# 8051.net
KiCad netlist of a schematic drawn in EAGLE
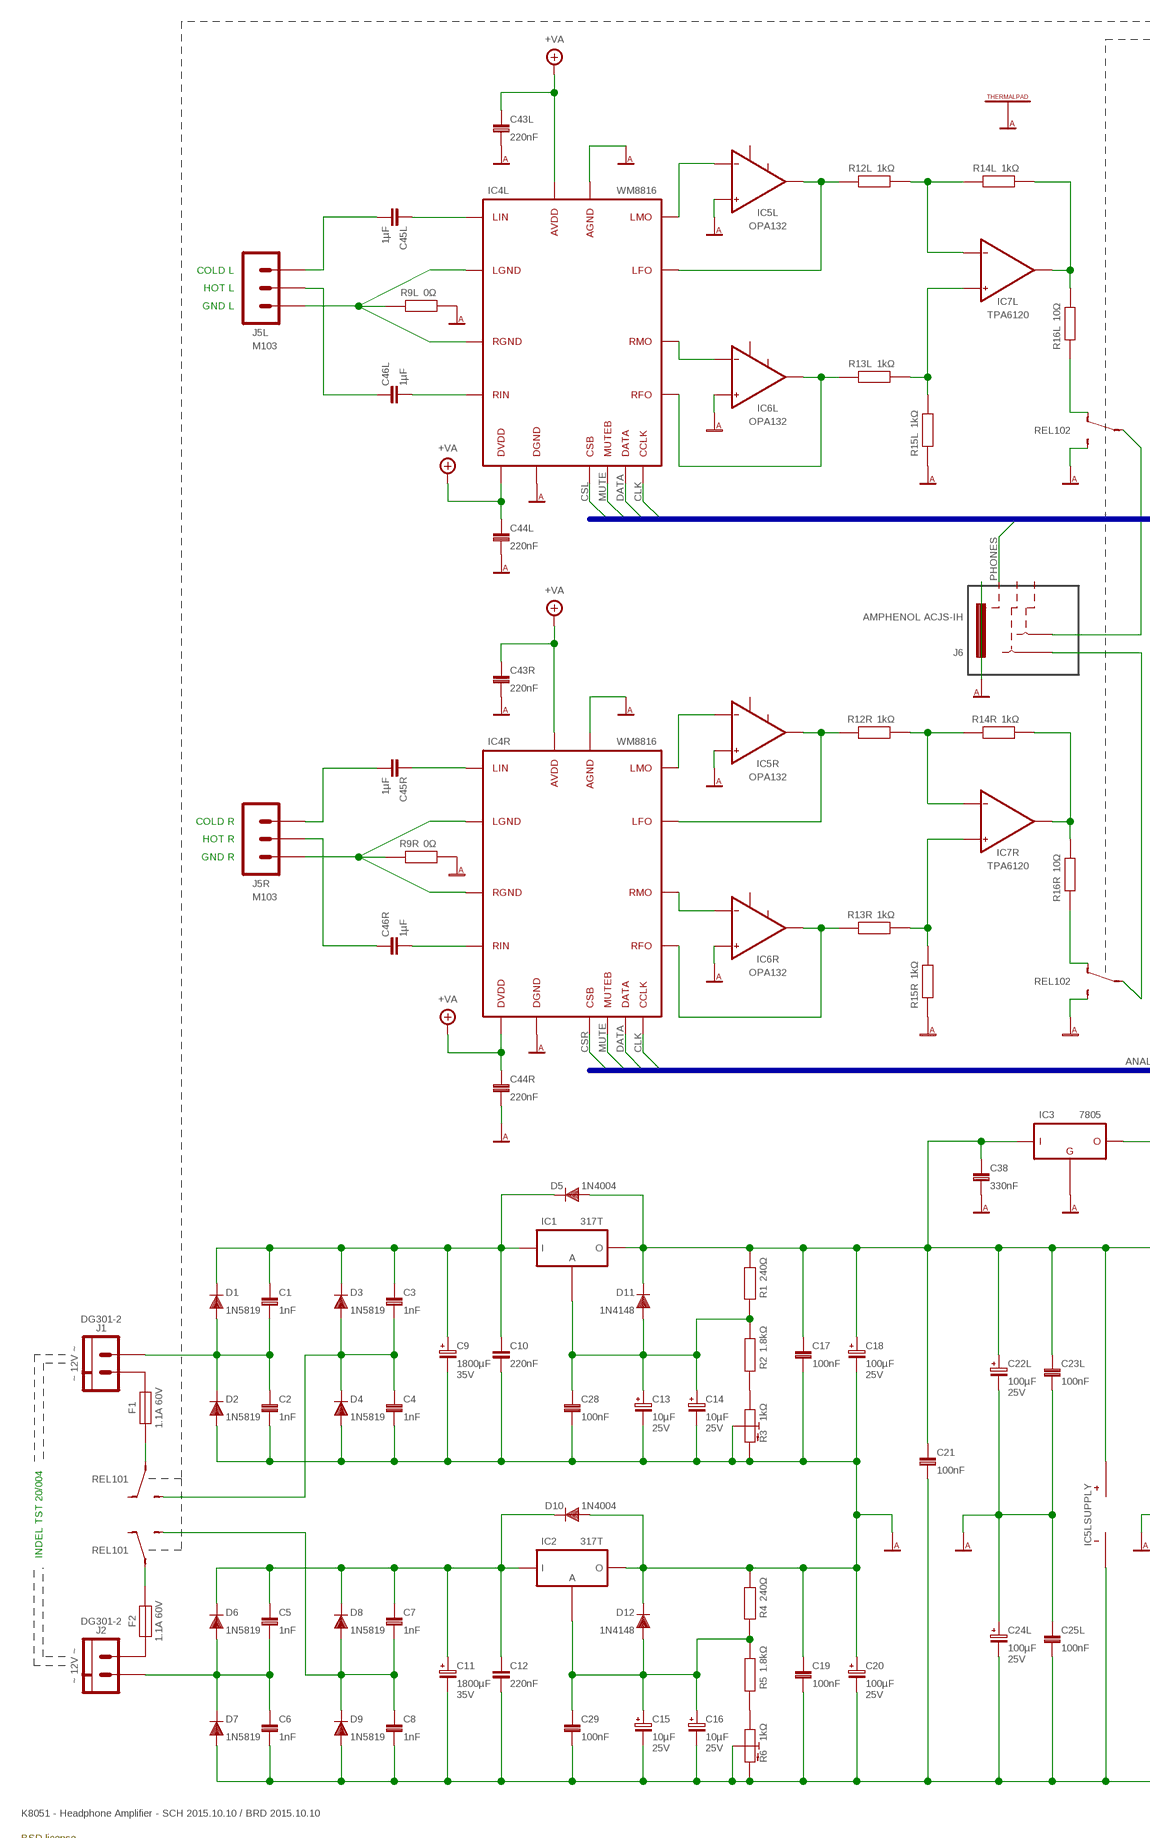
[diagram p0: schematic, sheet 1, part 1 of 2]
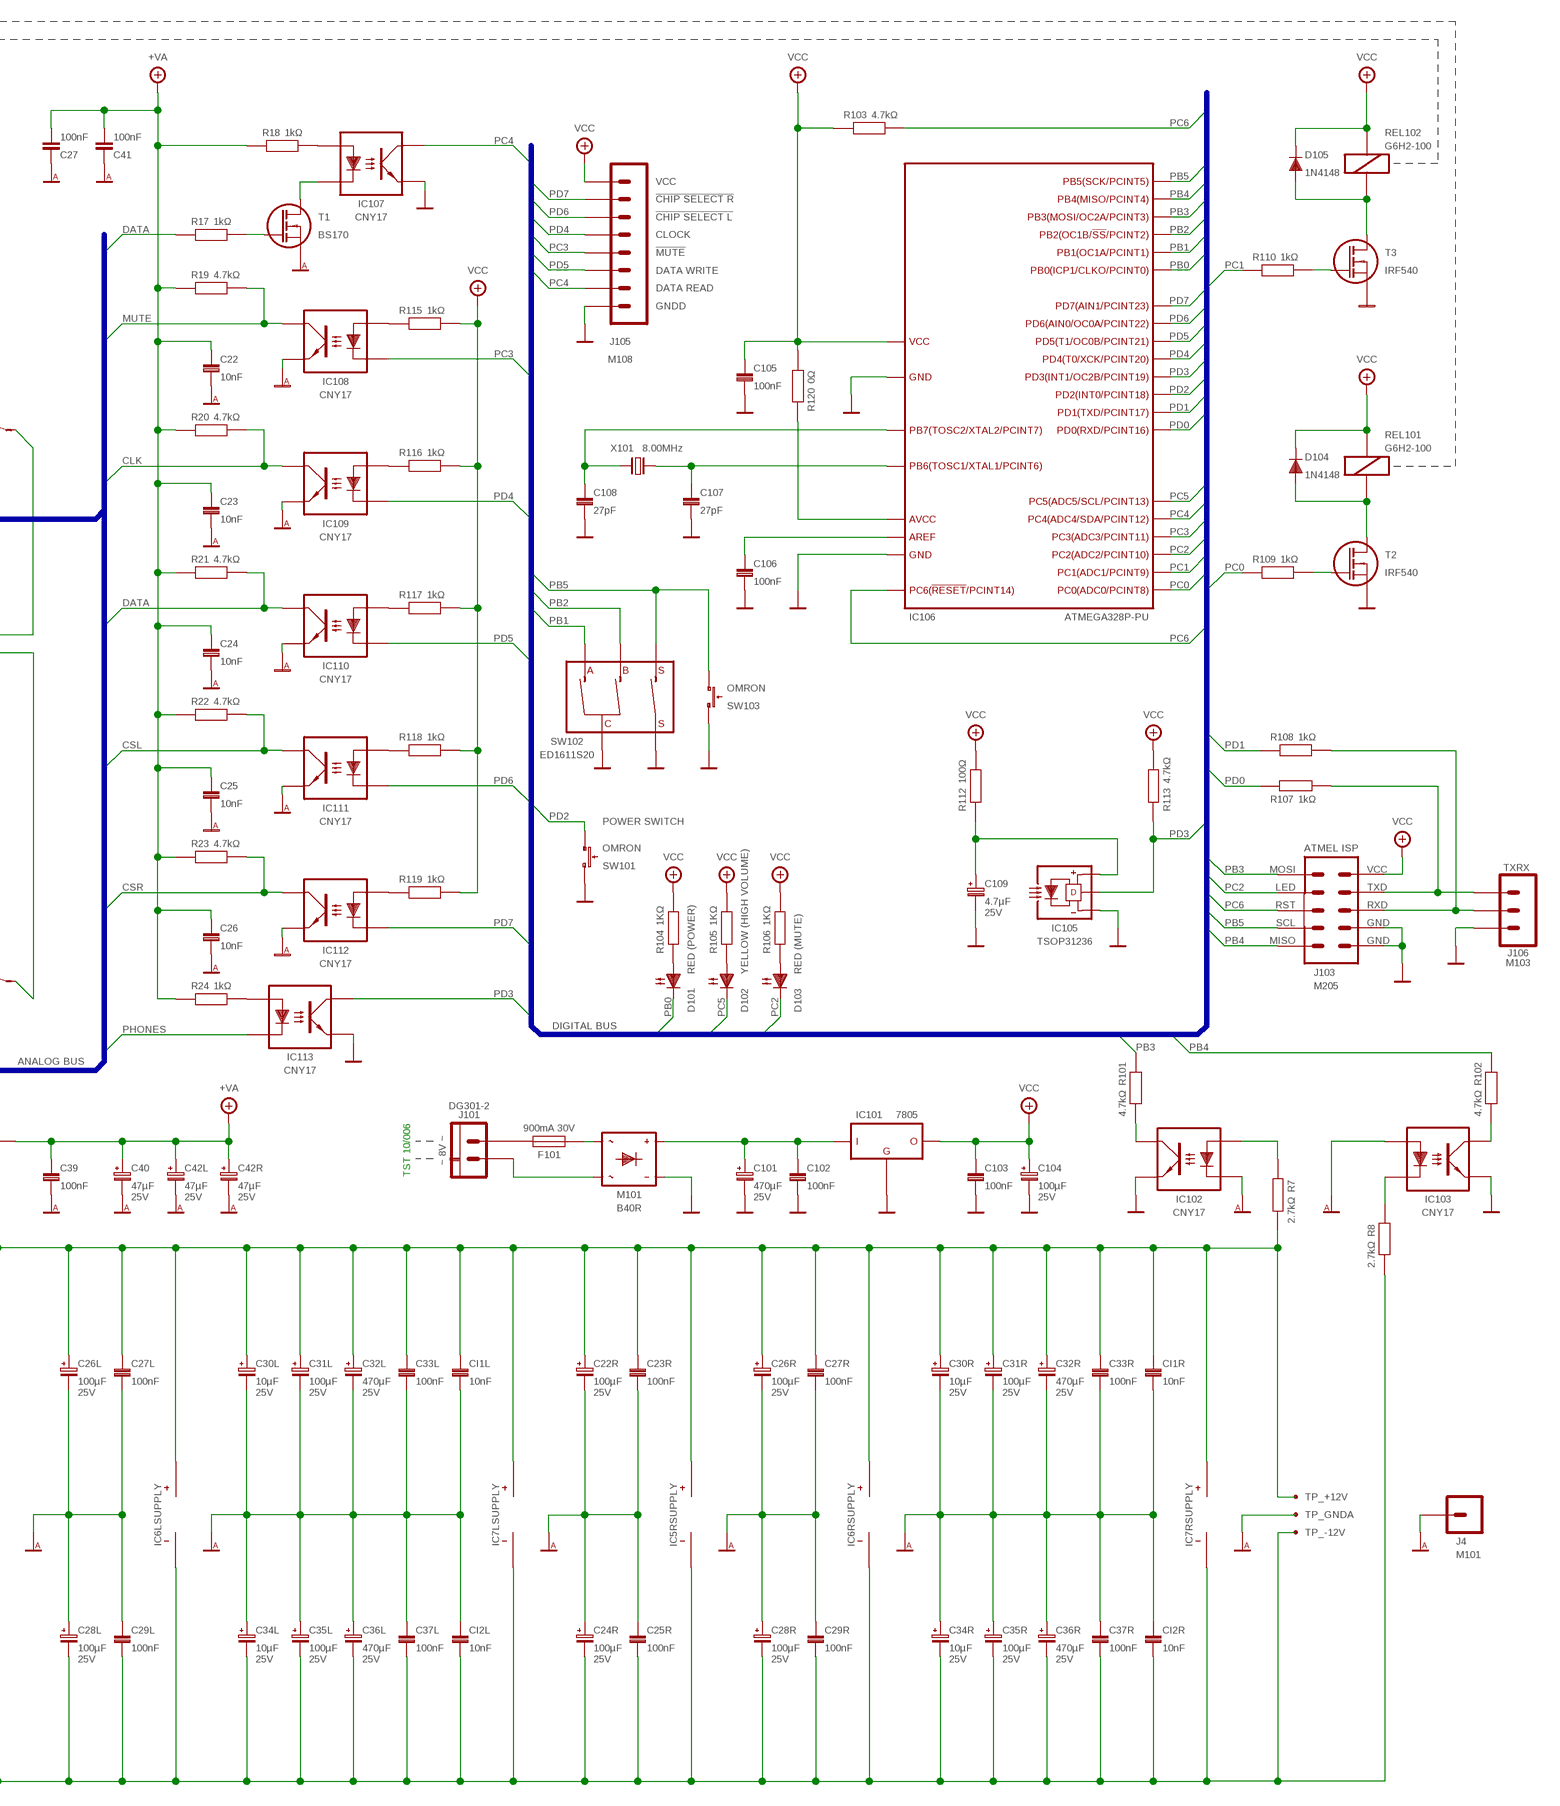
[diagram p1: schematic, sheet 1, part 2 of 2]

(export (version "E")
  (design (tool "Eeschema 10.0.6"))
  (components
    (comp (ref "C1")
      (value "1nF")
      (footprint "eagle-import:C075-032X103")
      (libsource (lib "eagle-import") (part "C075-032X103"))
    )
    (comp (ref "C2")
      (value "1nF")
      (footprint "eagle-import:C075-032X103")
      (libsource (lib "eagle-import") (part "C075-032X103"))
    )
    (comp (ref "C3")
      (value "1nF")
      (footprint "eagle-import:C075-032X103")
      (libsource (lib "eagle-import") (part "C075-032X103"))
    )
    (comp (ref "C4")
      (value "1nF")
      (footprint "eagle-import:C075-032X103")
      (libsource (lib "eagle-import") (part "C075-032X103"))
    )
    (comp (ref "C5")
      (value "1nF")
      (footprint "eagle-import:C075-032X103")
      (libsource (lib "eagle-import") (part "C075-032X103"))
    )
    (comp (ref "C6")
      (value "1nF")
      (footprint "eagle-import:C075-032X103")
      (libsource (lib "eagle-import") (part "C075-032X103"))
    )
    (comp (ref "C7")
      (value "1nF")
      (footprint "eagle-import:C075-032X103")
      (libsource (lib "eagle-import") (part "C075-032X103"))
    )
    (comp (ref "C8")
      (value "1nF")
      (footprint "eagle-import:C075-032X103")
      (libsource (lib "eagle-import") (part "C075-032X103"))
    )
    (comp (ref "C9")
      (value "1800µF")
      (footprint "eagle-import:E-160-250-075-08")
      (fields (field (name "VOLTAGE") "35V"))
      (libsource (lib "eagle-import") (part "FM1V182"))
    )
    (comp (ref "C10")
      (value "220nF")
      (footprint "eagle-import:C102-064X133")
      (libsource (lib "eagle-import") (part "C102-064X133"))
    )
    (comp (ref "C11")
      (value "1800µF")
      (footprint "eagle-import:E-160-250-075-08")
      (fields (field (name "VOLTAGE") "35V"))
      (libsource (lib "eagle-import") (part "FM1V182"))
    )
    (comp (ref "C12")
      (value "220nF")
      (footprint "eagle-import:C102-064X133")
      (libsource (lib "eagle-import") (part "C102-064X133"))
    )
    (comp (ref "C13")
      (value "10µF")
      (footprint "eagle-import:E-050-110-020-05")
      (fields (field (name "VOLTAGE") "25V") (field (name "VOLTAGE_1") "25V"))
      (libsource (lib "eagle-import") (part "FM1E470"))
    )
    (comp (ref "C14")
      (value "10µF")
      (footprint "eagle-import:E-050-110-020-05")
      (fields (field (name "VOLTAGE") "25V") (field (name "VOLTAGE_1") "25V"))
      (libsource (lib "eagle-import") (part "FM1E470"))
    )
    (comp (ref "C15")
      (value "10µF")
      (footprint "eagle-import:E-050-110-020-05")
      (fields (field (name "VOLTAGE") "25V") (field (name "VOLTAGE_1") "25V"))
      (libsource (lib "eagle-import") (part "FM1E470"))
    )
    (comp (ref "C16")
      (value "10µF")
      (footprint "eagle-import:E-050-110-020-05")
      (fields (field (name "VOLTAGE") "25V") (field (name "VOLTAGE_1") "25V"))
      (libsource (lib "eagle-import") (part "FM1E470"))
    )
    (comp (ref "C17")
      (value "100nF")
      (footprint "eagle-import:C075-042X103")
      (libsource (lib "eagle-import") (part "C075-042X103"))
    )
    (comp (ref "C18")
      (value "100µF")
      (footprint "eagle-import:E-063-112-025-05")
      (fields (field (name "VOLTAGE") "25V") (field (name "VOLTAGE_1") "25V"))
      (libsource (lib "eagle-import") (part "FM1E101"))
    )
    (comp (ref "C19")
      (value "100nF")
      (footprint "eagle-import:C075-042X103")
      (libsource (lib "eagle-import") (part "C075-042X103"))
    )
    (comp (ref "C20")
      (value "100µF")
      (footprint "eagle-import:E-063-112-025-05")
      (fields (field (name "VOLTAGE") "25V") (field (name "VOLTAGE_1") "25V"))
      (libsource (lib "eagle-import") (part "FM1E101"))
    )
    (comp (ref "C21")
      (value "100nF")
      (footprint "eagle-import:C075-042X103")
      (libsource (lib "eagle-import") (part "C075-042X103"))
    )
    (comp (ref "C22")
      (value "10nF")
      (footprint "eagle-import:C0805")
      (libsource (lib "eagle-import") (part "CC0805"))
    )
    (comp (ref "C22L")
      (value "100µF")
      (footprint "eagle-import:E-063-112-025-05")
      (fields (field (name "VOLTAGE") "25V") (field (name "VOLTAGE_1") "25V"))
      (libsource (lib "eagle-import") (part "FM1E101"))
    )
    (comp (ref "C22R")
      (value "100µF")
      (footprint "eagle-import:E-063-112-025-05")
      (fields (field (name "VOLTAGE") "25V") (field (name "VOLTAGE_1") "25V"))
      (libsource (lib "eagle-import") (part "FM1E101"))
    )
    (comp (ref "C23")
      (value "10nF")
      (footprint "eagle-import:C0805")
      (libsource (lib "eagle-import") (part "CC0805"))
    )
    (comp (ref "C23L")
      (value "100nF")
      (footprint "eagle-import:C075-042X103")
      (libsource (lib "eagle-import") (part "C075-042X103"))
    )
    (comp (ref "C23R")
      (value "100nF")
      (footprint "eagle-import:C075-042X103")
      (libsource (lib "eagle-import") (part "C075-042X103"))
    )
    (comp (ref "C24")
      (value "10nF")
      (footprint "eagle-import:C0805")
      (libsource (lib "eagle-import") (part "CC0805"))
    )
    (comp (ref "C24L")
      (value "100µF")
      (footprint "eagle-import:E-063-112-025-05")
      (fields (field (name "VOLTAGE") "25V") (field (name "VOLTAGE_1") "25V"))
      (libsource (lib "eagle-import") (part "FM1E101"))
    )
    (comp (ref "C24R")
      (value "100µF")
      (footprint "eagle-import:E-063-112-025-05")
      (fields (field (name "VOLTAGE") "25V") (field (name "VOLTAGE_1") "25V"))
      (libsource (lib "eagle-import") (part "FM1E101"))
    )
    (comp (ref "C25")
      (value "10nF")
      (footprint "eagle-import:C0805")
      (libsource (lib "eagle-import") (part "CC0805"))
    )
    (comp (ref "C25L")
      (value "100nF")
      (footprint "eagle-import:C075-042X103")
      (libsource (lib "eagle-import") (part "C075-042X103"))
    )
    (comp (ref "C25R")
      (value "100nF")
      (footprint "eagle-import:C075-042X103")
      (libsource (lib "eagle-import") (part "C075-042X103"))
    )
    (comp (ref "C26")
      (value "10nF")
      (footprint "eagle-import:C0805")
      (libsource (lib "eagle-import") (part "CC0805"))
    )
    (comp (ref "C26L")
      (value "100µF")
      (footprint "eagle-import:E-063-112-025-05")
      (fields (field (name "VOLTAGE") "25V") (field (name "VOLTAGE_1") "25V"))
      (libsource (lib "eagle-import") (part "FM1E101"))
    )
    (comp (ref "C26R")
      (value "100µF")
      (footprint "eagle-import:E-063-112-025-05")
      (fields (field (name "VOLTAGE") "25V") (field (name "VOLTAGE_1") "25V"))
      (libsource (lib "eagle-import") (part "FM1E101"))
    )
    (comp (ref "C27")
      (value "100nF")
      (footprint "eagle-import:C075-042X103")
      (libsource (lib "eagle-import") (part "C075-042X103"))
    )
    (comp (ref "C27L")
      (value "100nF")
      (footprint "eagle-import:C075-042X103")
      (libsource (lib "eagle-import") (part "C075-042X103"))
    )
    (comp (ref "C27R")
      (value "100nF")
      (footprint "eagle-import:C075-042X103")
      (libsource (lib "eagle-import") (part "C075-042X103"))
    )
    (comp (ref "C28")
      (value "100nF")
      (footprint "eagle-import:C1812")
      (libsource (lib "eagle-import") (part "CC1812"))
    )
    (comp (ref "C28L")
      (value "100µF")
      (footprint "eagle-import:E-063-112-025-05")
      (fields (field (name "VOLTAGE") "25V") (field (name "VOLTAGE_1") "25V"))
      (libsource (lib "eagle-import") (part "FM1E101"))
    )
    (comp (ref "C28R")
      (value "100µF")
      (footprint "eagle-import:E-063-112-025-05")
      (fields (field (name "VOLTAGE") "25V") (field (name "VOLTAGE_1") "25V"))
      (libsource (lib "eagle-import") (part "FM1E101"))
    )
    (comp (ref "C29")
      (value "100nF")
      (footprint "eagle-import:C1812")
      (libsource (lib "eagle-import") (part "CC1812"))
    )
    (comp (ref "C29L")
      (value "100nF")
      (footprint "eagle-import:C075-042X103")
      (libsource (lib "eagle-import") (part "C075-042X103"))
    )
    (comp (ref "C29R")
      (value "100nF")
      (footprint "eagle-import:C075-042X103")
      (libsource (lib "eagle-import") (part "C075-042X103"))
    )
    (comp (ref "C30L")
      (value "10µF")
      (footprint "eagle-import:E-050-110-020-05")
      (fields (field (name "VOLTAGE") "25V"))
      (libsource (lib "eagle-import") (part "FM1E470"))
    )
    (comp (ref "C30R")
      (value "10µF")
      (footprint "eagle-import:E-050-110-020-05")
      (fields (field (name "VOLTAGE") "25V"))
      (libsource (lib "eagle-import") (part "FM1E470"))
    )
    (comp (ref "C31L")
      (value "100µF")
      (footprint "eagle-import:E-063-112-025-05")
      (fields (field (name "VOLTAGE") "25V"))
      (libsource (lib "eagle-import") (part "FM1E101"))
    )
    (comp (ref "C31R")
      (value "100µF")
      (footprint "eagle-import:E-063-112-025-05")
      (fields (field (name "VOLTAGE") "25V"))
      (libsource (lib "eagle-import") (part "FM1E101"))
    )
    (comp (ref "C32L")
      (value "470µF")
      (footprint "eagle-import:E-100-160-050-06")
      (fields (field (name "VOLTAGE") "25V") (field (name "VOLTAGE_1") "25V"))
      (libsource (lib "eagle-import") (part "FM1E471"))
    )
    (comp (ref "C32R")
      (value "470µF")
      (footprint "eagle-import:E-100-160-050-06")
      (fields (field (name "VOLTAGE") "25V") (field (name "VOLTAGE_1") "25V"))
      (libsource (lib "eagle-import") (part "FM1E471"))
    )
    (comp (ref "C33L")
      (value "100nF")
      (footprint "eagle-import:C075-042X103")
      (libsource (lib "eagle-import") (part "C075-042X103"))
    )
    (comp (ref "C33R")
      (value "100nF")
      (footprint "eagle-import:C075-042X103")
      (libsource (lib "eagle-import") (part "C075-042X103"))
    )
    (comp (ref "C34L")
      (value "10µF")
      (footprint "eagle-import:E-050-110-020-05")
      (fields (field (name "VOLTAGE") "25V"))
      (libsource (lib "eagle-import") (part "FM1E470"))
    )
    (comp (ref "C34R")
      (value "10µF")
      (footprint "eagle-import:E-050-110-020-05")
      (fields (field (name "VOLTAGE") "25V"))
      (libsource (lib "eagle-import") (part "FM1E470"))
    )
    (comp (ref "C35L")
      (value "100µF")
      (footprint "eagle-import:E-063-112-025-05")
      (fields (field (name "VOLTAGE") "25V"))
      (libsource (lib "eagle-import") (part "FM1E101"))
    )
    (comp (ref "C35R")
      (value "100µF")
      (footprint "eagle-import:E-063-112-025-05")
      (fields (field (name "VOLTAGE") "25V"))
      (libsource (lib "eagle-import") (part "FM1E101"))
    )
    (comp (ref "C36L")
      (value "470µF")
      (footprint "eagle-import:E-100-160-050-06")
      (fields (field (name "VOLTAGE") "25V") (field (name "VOLTAGE_1") "25V"))
      (libsource (lib "eagle-import") (part "FM1E471"))
    )
    (comp (ref "C36R")
      (value "470µF")
      (footprint "eagle-import:E-100-160-050-06")
      (fields (field (name "VOLTAGE") "25V") (field (name "VOLTAGE_1") "25V"))
      (libsource (lib "eagle-import") (part "FM1E471"))
    )
    (comp (ref "C37L")
      (value "100nF")
      (footprint "eagle-import:C075-042X103")
      (libsource (lib "eagle-import") (part "C075-042X103"))
    )
    (comp (ref "C37R")
      (value "100nF")
      (footprint "eagle-import:C075-042X103")
      (libsource (lib "eagle-import") (part "C075-042X103"))
    )
    (comp (ref "C38")
      (value "330nF")
      (footprint "eagle-import:C1206")
      (libsource (lib "eagle-import") (part "CC1206"))
    )
    (comp (ref "C39")
      (value "100nF")
      (footprint "eagle-import:C1206")
      (libsource (lib "eagle-import") (part "CC1206"))
    )
    (comp (ref "C40")
      (value "47µF")
      (footprint "eagle-import:E-050-110-020-05")
      (fields (field (name "VOLTAGE") "25V") (field (name "VOLTAGE_1") "25V"))
      (libsource (lib "eagle-import") (part "FM1E470"))
    )
    (comp (ref "C41")
      (value "100nF")
      (footprint "eagle-import:C075-042X103")
      (libsource (lib "eagle-import") (part "C075-042X103"))
    )
    (comp (ref "C42L")
      (value "47µF")
      (footprint "eagle-import:E-050-110-020-05")
      (fields (field (name "VOLTAGE") "25V"))
      (libsource (lib "eagle-import") (part "FM1E470"))
    )
    (comp (ref "C42R")
      (value "47µF")
      (footprint "eagle-import:E-050-110-020-05")
      (fields (field (name "VOLTAGE") "25V"))
      (libsource (lib "eagle-import") (part "FM1E470"))
    )
    (comp (ref "C43L")
      (value "220nF")
      (footprint "eagle-import:C102-064X133")
      (libsource (lib "eagle-import") (part "C102-064X133"))
    )
    (comp (ref "C43R")
      (value "220nF")
      (footprint "eagle-import:C102-064X133")
      (libsource (lib "eagle-import") (part "C102-064X133"))
    )
    (comp (ref "C44L")
      (value "220nF")
      (footprint "eagle-import:C102-064X133")
      (libsource (lib "eagle-import") (part "C102-064X133"))
    )
    (comp (ref "C44R")
      (value "220nF")
      (footprint "eagle-import:C102-064X133")
      (libsource (lib "eagle-import") (part "C102-064X133"))
    )
    (comp (ref "C45L")
      (value "1µF")
      (footprint "eagle-import:C075-063X106")
      (libsource (lib "eagle-import") (part "C075-063X106"))
    )
    (comp (ref "C45R")
      (value "1µF")
      (footprint "eagle-import:C075-063X106")
      (libsource (lib "eagle-import") (part "C075-063X106"))
    )
    (comp (ref "C46L")
      (value "1µF")
      (footprint "eagle-import:C075-063X106")
      (libsource (lib "eagle-import") (part "C075-063X106"))
    )
    (comp (ref "C46R")
      (value "1µF")
      (footprint "eagle-import:C075-063X106")
      (libsource (lib "eagle-import") (part "C075-063X106"))
    )
    (comp (ref "C101")
      (value "470µF")
      (footprint "eagle-import:E-100-160-050-06")
      (fields (field (name "VOLTAGE") "25V") (field (name "VOLTAGE_1") "25V"))
      (libsource (lib "eagle-import") (part "FM1E471"))
    )
    (comp (ref "C102")
      (value "100nF")
      (footprint "eagle-import:C1206")
      (libsource (lib "eagle-import") (part "CC1206"))
    )
    (comp (ref "C103")
      (value "100nF")
      (footprint "eagle-import:C1206")
      (libsource (lib "eagle-import") (part "CC1206"))
    )
    (comp (ref "C104")
      (value "100µF")
      (footprint "eagle-import:E-063-112-025-05")
      (fields (field (name "VOLTAGE") "25V") (field (name "VOLTAGE_1") "25V"))
      (libsource (lib "eagle-import") (part "FM1E101"))
    )
    (comp (ref "C105")
      (value "100nF")
      (footprint "eagle-import:C1206")
      (libsource (lib "eagle-import") (part "CC1206"))
    )
    (comp (ref "C106")
      (value "100nF")
      (footprint "eagle-import:C1206")
      (libsource (lib "eagle-import") (part "CC1206"))
    )
    (comp (ref "C107")
      (value "27pF")
      (footprint "eagle-import:C1206")
      (libsource (lib "eagle-import") (part "CC1206"))
    )
    (comp (ref "C108")
      (value "27pF")
      (footprint "eagle-import:C1206")
      (libsource (lib "eagle-import") (part "CC1206"))
    )
    (comp (ref "C109")
      (value "4.7µF")
      (footprint "eagle-import:E-050-110-020-05")
      (fields (field (name "VOLTAGE") "25V") (field (name "VOLTAGE_1") "25V"))
      (libsource (lib "eagle-import") (part "FM1E470"))
    )
    (comp (ref "CI1L")
      (value "10nF")
      (footprint "eagle-import:C0805K")
      (libsource (lib "eagle-import") (part "CC0805K"))
    )
    (comp (ref "CI1R")
      (value "10nF")
      (footprint "eagle-import:C0805K")
      (libsource (lib "eagle-import") (part "CC0805K"))
    )
    (comp (ref "CI2L")
      (value "10nF")
      (footprint "eagle-import:C0805K")
      (libsource (lib "eagle-import") (part "CC0805K"))
    )
    (comp (ref "CI2R")
      (value "10nF")
      (footprint "eagle-import:C0805K")
      (libsource (lib "eagle-import") (part "CC0805K"))
    )
    (comp (ref "D1")
      (value "1N5819")
      (footprint "eagle-import:DO41-10")
      (libsource (lib "eagle-import") (part "1N4004"))
    )
    (comp (ref "D2")
      (value "1N5819")
      (footprint "eagle-import:DO41-10")
      (libsource (lib "eagle-import") (part "1N4004"))
    )
    (comp (ref "D3")
      (value "1N5819")
      (footprint "eagle-import:DO41-10")
      (libsource (lib "eagle-import") (part "1N4004"))
    )
    (comp (ref "D4")
      (value "1N5819")
      (footprint "eagle-import:DO41-10")
      (libsource (lib "eagle-import") (part "1N4004"))
    )
    (comp (ref "D5")
      (value "1N4004")
      (footprint "eagle-import:DO41-10")
      (libsource (lib "eagle-import") (part "1N4004"))
    )
    (comp (ref "D6")
      (value "1N5819")
      (footprint "eagle-import:DO41-10")
      (libsource (lib "eagle-import") (part "1N4004"))
    )
    (comp (ref "D7")
      (value "1N5819")
      (footprint "eagle-import:DO41-10")
      (libsource (lib "eagle-import") (part "1N4004"))
    )
    (comp (ref "D8")
      (value "1N5819")
      (footprint "eagle-import:DO41-10")
      (libsource (lib "eagle-import") (part "1N4004"))
    )
    (comp (ref "D9")
      (value "1N5819")
      (footprint "eagle-import:DO41-10")
      (libsource (lib "eagle-import") (part "1N4004"))
    )
    (comp (ref "D10")
      (value "1N4004")
      (footprint "eagle-import:DO41-10")
      (libsource (lib "eagle-import") (part "1N4004"))
    )
    (comp (ref "D11")
      (value "1N4148")
      (footprint "eagle-import:DO35-7")
      (libsource (lib "eagle-import") (part "1N4148DO35-7"))
    )
    (comp (ref "D12")
      (value "1N4148")
      (footprint "eagle-import:DO35-7")
      (libsource (lib "eagle-import") (part "1N4148DO35-7"))
    )
    (comp (ref "D101")
      (value "RED (POWER)")
      (footprint "eagle-import:LED3MM")
      (libsource (lib "eagle-import") (part "LED3MM"))
    )
    (comp (ref "D102")
      (value "YELLOW (HIGH VOLUME)")
      (footprint "eagle-import:LED3MM")
      (libsource (lib "eagle-import") (part "LED3MM"))
    )
    (comp (ref "D103")
      (value "RED (MUTE)")
      (footprint "eagle-import:LED3MM")
      (libsource (lib "eagle-import") (part "LED3MM"))
    )
    (comp (ref "D104")
      (value "1N4148")
      (footprint "eagle-import:DO35-7")
      (libsource (lib "eagle-import") (part "1N4148DO35-7"))
    )
    (comp (ref "D105")
      (value "1N4148")
      (footprint "eagle-import:DO35-7")
      (libsource (lib "eagle-import") (part "1N4148DO35-7"))
    )
    (comp (ref "F1")
      (value "1.1A 60V")
      (footprint "eagle-import:LITTELFUSE-60R110")
      (libsource (lib "eagle-import") (part "FUSE-LITTELFUSE-60R110"))
    )
    (comp (ref "F2")
      (value "1.1A 60V")
      (footprint "eagle-import:LITTELFUSE-60R110")
      (libsource (lib "eagle-import") (part "FUSE-LITTELFUSE-60R110"))
    )
    (comp (ref "F101")
      (value "900mA 30V")
      (footprint "eagle-import:LITTELFUSE-30R090")
      (libsource (lib "eagle-import") (part "FUSE-LITTELFUSE-30R090"))
    )
    (comp (ref "IC1")
      (value "317T")
      (footprint "eagle-import:TO220")
      (libsource (lib "eagle-import") (part "LM317TS"))
    )
    (comp (ref "IC2")
      (value "317T")
      (footprint "eagle-import:TO220")
      (libsource (lib "eagle-import") (part "LM317TS"))
    )
    (comp (ref "IC3")
      (value "7805")
      (footprint "eagle-import:TO220")
      (libsource (lib "eagle-import") (part "LM78XX-C"))
    )
    (comp (ref "IC4L")
      (value "WM8816")
      (footprint "eagle-import:SO16W")
      (libsource (lib "eagle-import") (part "WM8816"))
    )
    (comp (ref "IC4R")
      (value "WM8816")
      (footprint "eagle-import:SO16W")
      (libsource (lib "eagle-import") (part "WM8816"))
    )
    (comp (ref "IC5L")
      (value "OPA132")
      (footprint "eagle-import:DIL08")
      (libsource (lib "eagle-import") (part "OPA132"))
    )
    (comp (ref "IC5R")
      (value "OPA132")
      (footprint "eagle-import:DIL08")
      (libsource (lib "eagle-import") (part "OPA132"))
    )
    (comp (ref "IC6L")
      (value "OPA132")
      (footprint "eagle-import:DIL08")
      (libsource (lib "eagle-import") (part "OPA132"))
    )
    (comp (ref "IC6R")
      (value "OPA132")
      (footprint "eagle-import:DIL08")
      (libsource (lib "eagle-import") (part "OPA132"))
    )
    (comp (ref "IC7")
      (value "TPA6120")
      (footprint "eagle-import:SO20-POWERPAD")
      (libsource (lib "eagle-import") (part "TPA6120"))
    )
    (comp (ref "IC101")
      (value "7805")
      (footprint "eagle-import:TO220")
      (libsource (lib "eagle-import") (part "LM78XX-C"))
    )
    (comp (ref "IC102")
      (value "CNY17")
      (footprint "eagle-import:DIL06")
      (fields (field (name "MF") "VISHAY/TELEFUNKEN") (field (name "MPN") "CNY17F-3"))
      (libsource (lib "eagle-import") (part "CNY17F"))
    )
    (comp (ref "IC103")
      (value "CNY17")
      (footprint "eagle-import:DIL06")
      (fields (field (name "MF") "VISHAY/TELEFUNKEN") (field (name "MPN") "CNY17F-3"))
      (libsource (lib "eagle-import") (part "CNY17F"))
    )
    (comp (ref "IC105")
      (value "TSOP31236")
      (footprint "eagle-import:TSOP17XX")
      (libsource (lib "eagle-import") (part "TSOP1736"))
    )
    (comp (ref "IC106")
      (value "ATMEGA328P-PU")
      (footprint "eagle-import:DIP254P800X550-28B")
      (libsource (lib "eagle-import") (part "ATMEGA328P-PU"))
    )
    (comp (ref "IC107")
      (value "CNY17")
      (footprint "eagle-import:DIL06")
      (fields
        (field (name "MF") "VISHAY/TELEFUNKEN")
        (field (name "MPN") "CNY17F-3")
        (field (name "MF_1") "VISHAY/TELEFUNKEN")
        (field (name "MPN_1") "CNY17F-3")
        (field (name "OC_FARNELL") "1469473")
        (field (name "OC_NEWARK") "58K0172")
      )
      (libsource (lib "eagle-import") (part "CNY17F"))
    )
    (comp (ref "IC108")
      (value "CNY17")
      (footprint "eagle-import:DIL06")
      (fields
        (field (name "MF") "VISHAY/TELEFUNKEN")
        (field (name "MPN") "CNY17F-3")
        (field (name "MF_1") "VISHAY/TELEFUNKEN")
        (field (name "MPN_1") "CNY17F-3")
        (field (name "OC_FARNELL") "1469473")
        (field (name "OC_NEWARK") "58K0172")
      )
      (libsource (lib "eagle-import") (part "CNY17F"))
    )
    (comp (ref "IC109")
      (value "CNY17")
      (footprint "eagle-import:DIL06")
      (fields
        (field (name "MF") "VISHAY/TELEFUNKEN")
        (field (name "MPN") "CNY17F-3")
        (field (name "MF_1") "VISHAY/TELEFUNKEN")
        (field (name "MPN_1") "CNY17F-3")
        (field (name "OC_FARNELL") "1469473")
        (field (name "OC_NEWARK") "58K0172")
      )
      (libsource (lib "eagle-import") (part "CNY17F"))
    )
    (comp (ref "IC110")
      (value "CNY17")
      (footprint "eagle-import:DIL06")
      (fields
        (field (name "MF") "VISHAY/TELEFUNKEN")
        (field (name "MPN") "CNY17F-3")
        (field (name "MF_1") "VISHAY/TELEFUNKEN")
        (field (name "MPN_1") "CNY17F-3")
        (field (name "OC_FARNELL") "1469473")
        (field (name "OC_NEWARK") "58K0172")
      )
      (libsource (lib "eagle-import") (part "CNY17F"))
    )
    (comp (ref "IC111")
      (value "CNY17")
      (footprint "eagle-import:DIL06")
      (fields
        (field (name "MF") "VISHAY/TELEFUNKEN")
        (field (name "MPN") "CNY17F-3")
        (field (name "MF_1") "VISHAY/TELEFUNKEN")
        (field (name "MPN_1") "CNY17F-3")
        (field (name "OC_FARNELL") "1469473")
        (field (name "OC_NEWARK") "58K0172")
      )
      (libsource (lib "eagle-import") (part "CNY17F"))
    )
    (comp (ref "IC112")
      (value "CNY17")
      (footprint "eagle-import:DIL06")
      (fields
        (field (name "MF") "VISHAY/TELEFUNKEN")
        (field (name "MPN") "CNY17F-3")
        (field (name "MF_1") "VISHAY/TELEFUNKEN")
        (field (name "MPN_1") "CNY17F-3")
        (field (name "OC_FARNELL") "1469473")
        (field (name "OC_NEWARK") "58K0172")
      )
      (libsource (lib "eagle-import") (part "CNY17F"))
    )
    (comp (ref "IC113")
      (value "CNY17")
      (footprint "eagle-import:DIL06")
      (fields (field (name "MF") "VISHAY/TELEFUNKEN") (field (name "MPN") "CNY17F-3"))
      (libsource (lib "eagle-import") (part "CNY17F"))
    )
    (comp (ref "J1")
      (value "DG301-2")
      (footprint "eagle-import:DG301-2")
      (libsource (lib "eagle-import") (part "?-2DG301"))
    )
    (comp (ref "J2")
      (value "DG301-2")
      (footprint "eagle-import:DG301-2")
      (libsource (lib "eagle-import") (part "?-2DG301"))
    )
    (comp (ref "J4")
      (value "M101")
      (footprint "eagle-import:1-1")
      (libsource (lib "eagle-import") (part "1-1"))
    )
    (comp (ref "J5L")
      (value "M103")
      (footprint "eagle-import:1-3")
      (libsource (lib "eagle-import") (part "1-3"))
    )
    (comp (ref "J5R")
      (value "M103")
      (footprint "eagle-import:1-3")
      (libsource (lib "eagle-import") (part "1-3"))
    )
    (comp (ref "J6")
      (value "AMPHENOL ACJS-IH")
      (footprint "eagle-import:JACK-FEMALE-STEREO")
      (libsource (lib "eagle-import") (part "JACK-FEMALE-STEREO"))
    )
    (comp (ref "J101")
      (value "DG301-2")
      (footprint "eagle-import:DG301-2")
      (libsource (lib "eagle-import") (part "?-2DG301"))
    )
    (comp (ref "J103")
      (value "M205")
      (footprint "eagle-import:MM-10-V")
      (libsource (lib "eagle-import") (part "ATMEL-ISP-10-RXTX-V"))
    )
    (comp (ref "J105")
      (value "M108")
      (footprint "eagle-import:1-8")
      (libsource (lib "eagle-import") (part "1-8"))
    )
    (comp (ref "J106")
      (value "M103")
      (footprint "eagle-import:1-3")
      (libsource (lib "eagle-import") (part "1-3"))
    )
    (comp (ref "M101")
      (value "B40R")
      (footprint "eagle-import:RB1A")
      (libsource (lib "eagle-import") (part "B40C1500R"))
    )
    (comp (ref "R1")
      (value "240Ω")
      (footprint "eagle-import:R1206")
      (libsource (lib "eagle-import") (part "RR1206"))
    )
    (comp (ref "R2")
      (value "1.8kΩ")
      (footprint "eagle-import:R1206")
      (libsource (lib "eagle-import") (part "RR1206"))
    )
    (comp (ref "R3")
      (value "1kΩ")
      (footprint "eagle-import:POT_B64Y")
      (libsource (lib "eagle-import") (part "POTB64Y"))
    )
    (comp (ref "R4")
      (value "240Ω")
      (footprint "eagle-import:R1206")
      (libsource (lib "eagle-import") (part "RR1206"))
    )
    (comp (ref "R5")
      (value "1.8kΩ")
      (footprint "eagle-import:R1206")
      (libsource (lib "eagle-import") (part "RR1206"))
    )
    (comp (ref "R6")
      (value "1kΩ")
      (footprint "eagle-import:POT_B64Y")
      (libsource (lib "eagle-import") (part "POTB64Y"))
    )
    (comp (ref "R7")
      (value "2.7kΩ")
      (footprint "eagle-import:R1206")
      (libsource (lib "eagle-import") (part "RR1206"))
    )
    (comp (ref "R8")
      (value "2.7kΩ")
      (footprint "eagle-import:R1206")
      (libsource (lib "eagle-import") (part "RR1206"))
    )
    (comp (ref "R9L")
      (value "0Ω")
      (footprint "eagle-import:0204_5")
      (libsource (lib "eagle-import") (part "R0204/5"))
    )
    (comp (ref "R9R")
      (value "0Ω")
      (footprint "eagle-import:0204_5")
      (libsource (lib "eagle-import") (part "R0204/5"))
    )
    (comp (ref "R12L")
      (value "1kΩ")
      (footprint "eagle-import:0204_5")
      (libsource (lib "eagle-import") (part "R0204/5"))
    )
    (comp (ref "R12R")
      (value "1kΩ")
      (footprint "eagle-import:0204_5")
      (libsource (lib "eagle-import") (part "R0204/5"))
    )
    (comp (ref "R13L")
      (value "1kΩ")
      (footprint "eagle-import:0204_5")
      (libsource (lib "eagle-import") (part "R0204/5"))
    )
    (comp (ref "R13R")
      (value "1kΩ")
      (footprint "eagle-import:0204_5")
      (libsource (lib "eagle-import") (part "R0204/5"))
    )
    (comp (ref "R14L")
      (value "1kΩ")
      (footprint "eagle-import:0204_5")
      (libsource (lib "eagle-import") (part "R0204/5"))
    )
    (comp (ref "R14R")
      (value "1kΩ")
      (footprint "eagle-import:0204_5")
      (libsource (lib "eagle-import") (part "R0204/5"))
    )
    (comp (ref "R15L")
      (value "1kΩ")
      (footprint "eagle-import:TPA_RF")
      (libsource (lib "eagle-import") (part "R"))
    )
    (comp (ref "R15R")
      (value "1kΩ")
      (footprint "eagle-import:TPA_RF")
      (libsource (lib "eagle-import") (part "R"))
    )
    (comp (ref "R16L")
      (value "10Ω")
      (footprint "eagle-import:0204_5")
      (libsource (lib "eagle-import") (part "R0204/5"))
    )
    (comp (ref "R16R")
      (value "10Ω")
      (footprint "eagle-import:0204_5")
      (libsource (lib "eagle-import") (part "R0204/5"))
    )
    (comp (ref "R17")
      (value "1kΩ")
      (footprint "eagle-import:R1206")
      (libsource (lib "eagle-import") (part "RR1206"))
    )
    (comp (ref "R18")
      (value "1kΩ")
      (footprint "eagle-import:R1206")
      (libsource (lib "eagle-import") (part "RR1206"))
    )
    (comp (ref "R19")
      (value "4.7kΩ")
      (footprint "eagle-import:R1206")
      (libsource (lib "eagle-import") (part "RR1206"))
    )
    (comp (ref "R20")
      (value "4.7kΩ")
      (footprint "eagle-import:R1206")
      (libsource (lib "eagle-import") (part "RR1206"))
    )
    (comp (ref "R21")
      (value "4.7kΩ")
      (footprint "eagle-import:R1206")
      (libsource (lib "eagle-import") (part "RR1206"))
    )
    (comp (ref "R22")
      (value "4.7kΩ")
      (footprint "eagle-import:R1206")
      (libsource (lib "eagle-import") (part "RR1206"))
    )
    (comp (ref "R23")
      (value "4.7kΩ")
      (footprint "eagle-import:R1206")
      (libsource (lib "eagle-import") (part "RR1206"))
    )
    (comp (ref "R24")
      (value "1kΩ")
      (footprint "eagle-import:R1206")
      (libsource (lib "eagle-import") (part "RR1206"))
    )
    (comp (ref "R101")
      (value "4.7kΩ")
      (footprint "eagle-import:R1206")
      (libsource (lib "eagle-import") (part "RR1206"))
    )
    (comp (ref "R102")
      (value "4.7kΩ")
      (footprint "eagle-import:R1206")
      (libsource (lib "eagle-import") (part "RR1206"))
    )
    (comp (ref "R103")
      (value "4.7kΩ")
      (footprint "eagle-import:R1206")
      (libsource (lib "eagle-import") (part "RR1206"))
    )
    (comp (ref "R104")
      (value "1KΩ")
      (footprint "eagle-import:R1206")
      (libsource (lib "eagle-import") (part "RR1206"))
    )
    (comp (ref "R105")
      (value "1KΩ")
      (footprint "eagle-import:R1206")
      (libsource (lib "eagle-import") (part "RR1206"))
    )
    (comp (ref "R106")
      (value "1KΩ")
      (footprint "eagle-import:R1206")
      (libsource (lib "eagle-import") (part "RR1206"))
    )
    (comp (ref "R107")
      (value "1kΩ")
      (footprint "eagle-import:R1206")
      (libsource (lib "eagle-import") (part "RR1206"))
    )
    (comp (ref "R108")
      (value "1kΩ")
      (footprint "eagle-import:R1206")
      (libsource (lib "eagle-import") (part "RR1206"))
    )
    (comp (ref "R109")
      (value "1kΩ")
      (footprint "eagle-import:R1206")
      (libsource (lib "eagle-import") (part "RR1206"))
    )
    (comp (ref "R110")
      (value "1kΩ")
      (footprint "eagle-import:R1206")
      (libsource (lib "eagle-import") (part "RR1206"))
    )
    (comp (ref "R112")
      (value "100Ω")
      (footprint "eagle-import:R1206")
      (libsource (lib "eagle-import") (part "RR1206"))
    )
    (comp (ref "R113")
      (value "4.7kΩ")
      (footprint "eagle-import:R1206")
      (libsource (lib "eagle-import") (part "RR1206"))
    )
    (comp (ref "R115")
      (value "1kΩ")
      (footprint "eagle-import:R1206")
      (libsource (lib "eagle-import") (part "RR1206"))
    )
    (comp (ref "R116")
      (value "1kΩ")
      (footprint "eagle-import:R1206")
      (libsource (lib "eagle-import") (part "RR1206"))
    )
    (comp (ref "R117")
      (value "1kΩ")
      (footprint "eagle-import:R1206")
      (libsource (lib "eagle-import") (part "RR1206"))
    )
    (comp (ref "R118")
      (value "1kΩ")
      (footprint "eagle-import:R1206")
      (libsource (lib "eagle-import") (part "RR1206"))
    )
    (comp (ref "R119")
      (value "1kΩ")
      (footprint "eagle-import:R1206")
      (libsource (lib "eagle-import") (part "RR1206"))
    )
    (comp (ref "R120")
      (value "0Ω")
      (footprint "eagle-import:R1206")
      (libsource (lib "eagle-import") (part "RR1206"))
    )
    (comp (ref "REL101")
      (value "G6H2-100")
      (footprint "eagle-import:G6H2-100")
      (libsource (lib "eagle-import") (part "G6H2-100"))
    )
    (comp (ref "REL102")
      (value "G6H2-100")
      (footprint "eagle-import:G6H2-100")
      (libsource (lib "eagle-import") (part "G6H2-100"))
    )
    (comp (ref "SW101")
      (value "OMRON")
      (footprint "eagle-import:B3F-31XX")
      (libsource (lib "eagle-import") (part "10-XXVERT"))
    )
    (comp (ref "SW102")
      (value "ED1611S20")
      (footprint "eagle-import:ED1611S-20")
      (libsource (lib "eagle-import") (part "ED1611S20"))
    )
    (comp (ref "SW103")
      (value "OMRON")
      (footprint "eagle-import:B3F-31XX")
      (libsource (lib "eagle-import") (part "10-XXVERT"))
    )
    (comp (ref "T1")
      (value "BS170")
      (footprint "eagle-import:TO92-DGS-BENT")
      (libsource (lib "eagle-import") (part "BS170BENT"))
    )
    (comp (ref "T2")
      (value "IRF540")
      (footprint "eagle-import:TO220-GDS")
      (libsource (lib "eagle-import") (part "IRF540"))
    )
    (comp (ref "T3")
      (value "IRF540")
      (footprint "eagle-import:TO220-GDS")
      (libsource (lib "eagle-import") (part "IRF540"))
    )
    (comp (ref "TP_+12V")
      (value "TP")
      (footprint "eagle-import:TP")
      (libsource (lib "eagle-import") (part "TP"))
    )
    (comp (ref "TP_-12V")
      (value "TP")
      (footprint "eagle-import:TP")
      (libsource (lib "eagle-import") (part "TP"))
    )
    (comp (ref "TP_GNDA")
      (value "TP")
      (footprint "eagle-import:TP")
      (libsource (lib "eagle-import") (part "TP"))
    )
    (comp (ref "X101")
      (value "8.00MHz")
      (footprint "eagle-import:HC49_S")
      (libsource (lib "eagle-import") (part "CRYSTALHC49S"))
    )
  )
  (nets
    (net (code "1") (name "+VA") (class "Default")
      (node (ref "C22") (pin "1") (pinfunction "1_1") (pintype "passive"))
      (node (ref "C23") (pin "1") (pinfunction "1_1") (pintype "passive"))
      (node (ref "C24") (pin "1") (pinfunction "1_1") (pintype "passive"))
      (node (ref "C25") (pin "1") (pinfunction "1_1") (pintype "passive"))
      (node (ref "C26") (pin "1") (pinfunction "1_1") (pintype "passive"))
      (node (ref "C27") (pin "2") (pinfunction "2_2") (pintype "passive"))
      (node (ref "C39") (pin "1") (pinfunction "1_1") (pintype "passive"))
      (node (ref "C40") (pin "+") (pinfunction "+_+") (pintype "passive"))
      (node (ref "C41") (pin "2") (pinfunction "2_2") (pintype "passive"))
      (node (ref "C42L") (pin "+") (pinfunction "+_+") (pintype "passive"))
      (node (ref "C42R") (pin "+") (pinfunction "+_+") (pintype "passive"))
      (node (ref "C43L") (pin "1") (pinfunction "1_1") (pintype "passive"))
      (node (ref "C43R") (pin "1") (pinfunction "1_1") (pintype "passive"))
      (node (ref "C44L") (pin "1") (pinfunction "1_1") (pintype "passive"))
      (node (ref "C44R") (pin "1") (pinfunction "1_1") (pintype "passive"))
      (node (ref "IC3") (pin "3") (pinfunction "OUT_3") (pintype "passive"))
      (node (ref "IC4L") (pin "1") (pinfunction "AVDD_1") (pintype "bidirectional"))
      (node (ref "IC4L") (pin "7") (pinfunction "DVDD_7") (pintype "bidirectional"))
      (node (ref "IC4R") (pin "1") (pinfunction "AVDD_1") (pintype "bidirectional"))
      (node (ref "IC4R") (pin "7") (pinfunction "DVDD_7") (pintype "bidirectional"))
      (node (ref "R18") (pin "1") (pinfunction "1_1") (pintype "passive"))
      (node (ref "R19") (pin "1") (pinfunction "1_1") (pintype "passive"))
      (node (ref "R20") (pin "1") (pinfunction "1_1") (pintype "passive"))
      (node (ref "R21") (pin "1") (pinfunction "1_1") (pintype "passive"))
      (node (ref "R22") (pin "1") (pinfunction "1_1") (pintype "passive"))
      (node (ref "R23") (pin "1") (pinfunction "1_1") (pintype "passive"))
      (node (ref "R24") (pin "1") (pinfunction "1_1") (pintype "passive"))
    )
    (net (code "2") (name "/CLK") (class "Default")
      (node (ref "IC109") (pin "5") (pinfunction "COL_5") (pintype "passive"))
      (node (ref "IC4L") (pin "10") (pinfunction "CCLK_10") (pintype "bidirectional"))
      (node (ref "IC4R") (pin "10") (pinfunction "CCLK_10") (pintype "bidirectional"))
      (node (ref "R20") (pin "2") (pinfunction "2_2") (pintype "passive"))
    )
    (net (code "3") (name "/CSL") (class "Default")
      (node (ref "IC111") (pin "5") (pinfunction "COL_5") (pintype "passive"))
      (node (ref "IC4L") (pin "6") (pinfunction "CSB_6") (pintype "bidirectional"))
      (node (ref "R22") (pin "2") (pinfunction "2_2") (pintype "passive"))
    )
    (net (code "4") (name "/CSR") (class "Default")
      (node (ref "IC112") (pin "5") (pinfunction "COL_5") (pintype "passive"))
      (node (ref "IC4R") (pin "6") (pinfunction "CSB_6") (pintype "bidirectional"))
      (node (ref "R23") (pin "2") (pinfunction "2_2") (pintype "passive"))
    )
    (net (code "5") (name "/DATA") (class "Default")
      (node (ref "IC110") (pin "5") (pinfunction "COL_5") (pintype "passive"))
      (node (ref "IC4L") (pin "9") (pinfunction "DATA_9") (pintype "bidirectional"))
      (node (ref "IC4R") (pin "9") (pinfunction "DATA_9") (pintype "bidirectional"))
      (node (ref "R17") (pin "1") (pinfunction "1_1") (pintype "passive"))
      (node (ref "R21") (pin "2") (pinfunction "2_2") (pintype "passive"))
    )
    (net (code "6") (name "/MUTE") (class "Default")
      (node (ref "IC108") (pin "5") (pinfunction "COL_5") (pintype "passive"))
      (node (ref "IC4L") (pin "8") (pinfunction "MUTEB_8") (pintype "bidirectional"))
      (node (ref "IC4R") (pin "8") (pinfunction "MUTEB_8") (pintype "bidirectional"))
      (node (ref "R19") (pin "2") (pinfunction "2_2") (pintype "passive"))
    )
    (net (code "7") (name "/PB0") (class "Default")
      (node (ref "D101") (pin "K") (pinfunction "C_K") (pintype "passive"))
      (node (ref "IC106") (pin "14") (pinfunction "PB0_14") (pintype "bidirectional"))
    )
    (net (code "8") (name "/PB1") (class "Default")
      (node (ref "IC106") (pin "15") (pinfunction "PB1_15") (pintype "bidirectional"))
      (node (ref "SW102") (pin "A") (pinfunction "A_A") (pintype "bidirectional"))
    )
    (net (code "9") (name "/PB2") (class "Default")
      (node (ref "IC106") (pin "16") (pinfunction "PB2_16") (pintype "bidirectional"))
      (node (ref "SW102") (pin "B") (pinfunction "B_B") (pintype "bidirectional"))
    )
    (net (code "10") (name "/PB3") (class "Default")
      (node (ref "IC106") (pin "17") (pinfunction "PB3_17") (pintype "bidirectional"))
      (node (ref "J103") (pin "1") (pinfunction "MOSI_1") (pintype "bidirectional"))
      (node (ref "R101") (pin "1") (pinfunction "1_1") (pintype "passive"))
    )
    (net (code "11") (name "/PB4") (class "Default")
      (node (ref "IC106") (pin "18") (pinfunction "PB4_18") (pintype "bidirectional"))
      (node (ref "J103") (pin "9") (pinfunction "MISO_9") (pintype "bidirectional"))
      (node (ref "R102") (pin "1") (pinfunction "1_1") (pintype "passive"))
    )
    (net (code "12") (name "/PB5") (class "Default")
      (node (ref "IC106") (pin "19") (pinfunction "PB5_19") (pintype "bidirectional"))
      (node (ref "J103") (pin "7") (pinfunction "SCL_7") (pintype "bidirectional"))
      (node (ref "SW102") (pin "S1") (pinfunction "S1_S1") (pintype "bidirectional"))
      (node (ref "SW103") (pin "1") (pinfunction "P_1") (pintype "passive"))
    )
    (net (code "13") (name "/PC0") (class "Default")
      (node (ref "IC106") (pin "23") (pinfunction "PC0_23") (pintype "bidirectional"))
      (node (ref "R109") (pin "1") (pinfunction "1_1") (pintype "passive"))
    )
    (net (code "14") (name "/PC1") (class "Default")
      (node (ref "IC106") (pin "24") (pinfunction "PC1_24") (pintype "bidirectional"))
      (node (ref "R110") (pin "1") (pinfunction "1_1") (pintype "passive"))
    )
    (net (code "15") (name "/PC2") (class "Default")
      (node (ref "D103") (pin "K") (pinfunction "C_K") (pintype "passive"))
      (node (ref "IC106") (pin "25") (pinfunction "PC2_25") (pintype "bidirectional"))
      (node (ref "J103") (pin "3") (pinfunction "LED_3") (pintype "bidirectional"))
    )
    (net (code "16") (name "/PC3") (class "Default")
      (node (ref "IC106") (pin "26") (pinfunction "PC3_26") (pintype "bidirectional"))
      (node (ref "IC108") (pin "2") (pinfunction "C_2") (pintype "passive"))
      (node (ref "J105") (pin "4") (pinfunction "4_4") (pintype "passive"))
    )
    (net (code "17") (name "/PC4") (class "Default")
      (node (ref "IC106") (pin "27") (pinfunction "PC4_27") (pintype "bidirectional"))
      (node (ref "IC107") (pin "5") (pinfunction "COL_5") (pintype "passive"))
      (node (ref "J105") (pin "2") (pinfunction "2_2") (pintype "passive"))
    )
    (net (code "18") (name "/PC5") (class "Default")
      (node (ref "D102") (pin "K") (pinfunction "C_K") (pintype "passive"))
      (node (ref "IC106") (pin "28") (pinfunction "PC5_28") (pintype "bidirectional"))
    )
    (net (code "19") (name "/PC6") (class "Default")
      (node (ref "IC106") (pin "1") (pinfunction "PC6_1") (pintype "bidirectional"))
      (node (ref "J103") (pin "5") (pinfunction "RST_5") (pintype "bidirectional"))
      (node (ref "R103") (pin "2") (pinfunction "2_2") (pintype "passive"))
    )
    (net (code "20") (name "/PD0") (class "Default")
      (node (ref "IC106") (pin "2") (pinfunction "PD0_2") (pintype "bidirectional"))
      (node (ref "R107") (pin "1") (pinfunction "1_1") (pintype "passive"))
    )
    (net (code "21") (name "/PD1") (class "Default")
      (node (ref "IC106") (pin "3") (pinfunction "PD1_3") (pintype "bidirectional"))
      (node (ref "R108") (pin "1") (pinfunction "1_1") (pintype "passive"))
    )
    (net (code "22") (name "/PD2") (class "Default")
      (node (ref "IC106") (pin "4") (pinfunction "PD2_4") (pintype "bidirectional"))
      (node (ref "SW101") (pin "1") (pinfunction "P_1") (pintype "passive"))
    )
    (net (code "23") (name "/PD3") (class "Default")
      (node (ref "IC105") (pin "OUT") (pinfunction "OUT_OUT") (pintype "bidirectional"))
      (node (ref "IC106") (pin "5") (pinfunction "PD3_5") (pintype "bidirectional"))
      (node (ref "IC113") (pin "5") (pinfunction "COL_5") (pintype "passive"))
      (node (ref "R113") (pin "2") (pinfunction "2_2") (pintype "passive"))
    )
    (net (code "24") (name "/PD4") (class "Default")
      (node (ref "IC106") (pin "6") (pinfunction "PD4_6") (pintype "bidirectional"))
      (node (ref "IC109") (pin "2") (pinfunction "C_2") (pintype "passive"))
      (node (ref "J105") (pin "5") (pinfunction "5_5") (pintype "passive"))
    )
    (net (code "25") (name "/PD5") (class "Default")
      (node (ref "IC106") (pin "11") (pinfunction "PD5_11") (pintype "bidirectional"))
      (node (ref "IC110") (pin "2") (pinfunction "C_2") (pintype "passive"))
      (node (ref "J105") (pin "3") (pinfunction "3_3") (pintype "passive"))
    )
    (net (code "26") (name "/PD6") (class "Default")
      (node (ref "IC106") (pin "12") (pinfunction "PD6_12") (pintype "bidirectional"))
      (node (ref "IC111") (pin "2") (pinfunction "C_2") (pintype "passive"))
      (node (ref "J105") (pin "6") (pinfunction "6_6") (pintype "passive"))
    )
    (net (code "27") (name "/PD7") (class "Default")
      (node (ref "IC106") (pin "13") (pinfunction "PD7_13") (pintype "bidirectional"))
      (node (ref "IC112") (pin "2") (pinfunction "C_2") (pintype "passive"))
      (node (ref "J105") (pin "7") (pinfunction "7_7") (pintype "passive"))
    )
    (net (code "28") (name "/PHONES") (class "Default")
      (node (ref "IC113") (pin "2") (pinfunction "C_2") (pintype "passive"))
      (node (ref "J6") (pin "GOFF") (pinfunction "GOFF_GOFF") (pintype "bidirectional"))
    )
    (net (code "29") (name "GND") (class "Default")
      (node (ref "C101") (pin "-") (pinfunction "-_-") (pintype "passive"))
      (node (ref "C102") (pin "2") (pinfunction "2_2") (pintype "passive"))
      (node (ref "C103") (pin "2") (pinfunction "2_2") (pintype "passive"))
      (node (ref "C104") (pin "-") (pinfunction "-_-") (pintype "passive"))
      (node (ref "C105") (pin "2") (pinfunction "2_2") (pintype "passive"))
      (node (ref "C106") (pin "2") (pinfunction "2_2") (pintype "passive"))
      (node (ref "C107") (pin "2") (pinfunction "2_2") (pintype "passive"))
      (node (ref "C108") (pin "2") (pinfunction "2_2") (pintype "passive"))
      (node (ref "C109") (pin "-") (pinfunction "-_-") (pintype "passive"))
      (node (ref "IC101") (pin "2") (pinfunction "GND_2") (pintype "passive"))
      (node (ref "IC102") (pin "4") (pinfunction "EMIT_4") (pintype "passive"))
      (node (ref "IC103") (pin "4") (pinfunction "EMIT_4") (pintype "passive"))
      (node (ref "IC105") (pin "GND") (pinfunction "GND_GND") (pintype "bidirectional"))
      (node (ref "IC106") (pin "22") (pinfunction "GND_22") (pintype "power_in"))
      (node (ref "IC106") (pin "8") (pinfunction "GND_8") (pintype "power_in"))
      (node (ref "IC107") (pin "4") (pinfunction "EMIT_4") (pintype "passive"))
      (node (ref "IC113") (pin "4") (pinfunction "EMIT_4") (pintype "passive"))
      (node (ref "J103") (pin "10") (pinfunction "GND_10") (pintype "power_in"))
      (node (ref "J103") (pin "8") (pinfunction "GND_8") (pintype "power_in"))
      (node (ref "J105") (pin "1") (pinfunction "1_1") (pintype "passive"))
      (node (ref "J106") (pin "1") (pinfunction "1_1") (pintype "passive"))
      (node (ref "M101") (pin "-") (pinfunction "-_-") (pintype "passive"))
      (node (ref "SW101") (pin "2") (pinfunction "S_2") (pintype "passive"))
      (node (ref "SW102") (pin "C") (pinfunction "C_C") (pintype "bidirectional"))
      (node (ref "SW102") (pin "S2") (pinfunction "S2_S2") (pintype "bidirectional"))
      (node (ref "SW103") (pin "2") (pinfunction "S_2") (pintype "passive"))
      (node (ref "T2") (pin "S") (pinfunction "S_S") (pintype "passive"))
      (node (ref "T3") (pin "S") (pinfunction "S_S") (pintype "passive"))
    )
    (net (code "30") (name "GNDA") (class "Default")
      (node (ref "C10") (pin "1") (pinfunction "1_1") (pintype "passive"))
      (node (ref "C13") (pin "-") (pinfunction "-_-") (pintype "passive"))
      (node (ref "C14") (pin "-") (pinfunction "-_-") (pintype "passive"))
      (node (ref "C17") (pin "2") (pinfunction "2_2") (pintype "passive"))
      (node (ref "C18") (pin "-") (pinfunction "-_-") (pintype "passive"))
      (node (ref "C19") (pin "1") (pinfunction "1_1") (pintype "passive"))
      (node (ref "C2") (pin "2") (pinfunction "2_2") (pintype "passive"))
      (node (ref "C20") (pin "+") (pinfunction "+_+") (pintype "passive"))
      (node (ref "C22") (pin "2") (pinfunction "2_2") (pintype "passive"))
      (node (ref "C22L") (pin "-") (pinfunction "-_-") (pintype "passive"))
      (node (ref "C22R") (pin "-") (pinfunction "-_-") (pintype "passive"))
      (node (ref "C23") (pin "2") (pinfunction "2_2") (pintype "passive"))
      (node (ref "C23L") (pin "2") (pinfunction "2_2") (pintype "passive"))
      (node (ref "C23R") (pin "2") (pinfunction "2_2") (pintype "passive"))
      (node (ref "C24") (pin "2") (pinfunction "2_2") (pintype "passive"))
      (node (ref "C24L") (pin "+") (pinfunction "+_+") (pintype "passive"))
      (node (ref "C24R") (pin "+") (pinfunction "+_+") (pintype "passive"))
      (node (ref "C25") (pin "2") (pinfunction "2_2") (pintype "passive"))
      (node (ref "C25L") (pin "1") (pinfunction "1_1") (pintype "passive"))
      (node (ref "C25R") (pin "1") (pinfunction "1_1") (pintype "passive"))
      (node (ref "C26") (pin "2") (pinfunction "2_2") (pintype "passive"))
      (node (ref "C26L") (pin "-") (pinfunction "-_-") (pintype "passive"))
      (node (ref "C26R") (pin "-") (pinfunction "-_-") (pintype "passive"))
      (node (ref "C27") (pin "1") (pinfunction "1_1") (pintype "passive"))
      (node (ref "C27L") (pin "2") (pinfunction "2_2") (pintype "passive"))
      (node (ref "C27R") (pin "2") (pinfunction "2_2") (pintype "passive"))
      (node (ref "C28") (pin "2") (pinfunction "2_2") (pintype "passive"))
      (node (ref "C28L") (pin "+") (pinfunction "+_+") (pintype "passive"))
      (node (ref "C28R") (pin "+") (pinfunction "+_+") (pintype "passive"))
      (node (ref "C29L") (pin "1") (pinfunction "1_1") (pintype "passive"))
      (node (ref "C29R") (pin "1") (pinfunction "1_1") (pintype "passive"))
      (node (ref "C30L") (pin "-") (pinfunction "-_-") (pintype "passive"))
      (node (ref "C30R") (pin "-") (pinfunction "-_-") (pintype "passive"))
      (node (ref "C31L") (pin "-") (pinfunction "-_-") (pintype "passive"))
      (node (ref "C31R") (pin "-") (pinfunction "-_-") (pintype "passive"))
      (node (ref "C32L") (pin "-") (pinfunction "-_-") (pintype "passive"))
      (node (ref "C32R") (pin "-") (pinfunction "-_-") (pintype "passive"))
      (node (ref "C33L") (pin "2") (pinfunction "2_2") (pintype "passive"))
      (node (ref "C33R") (pin "2") (pinfunction "2_2") (pintype "passive"))
      (node (ref "C34L") (pin "+") (pinfunction "+_+") (pintype "passive"))
      (node (ref "C34R") (pin "+") (pinfunction "+_+") (pintype "passive"))
      (node (ref "C35L") (pin "+") (pinfunction "+_+") (pintype "passive"))
      (node (ref "C35R") (pin "+") (pinfunction "+_+") (pintype "passive"))
      (node (ref "C36L") (pin "+") (pinfunction "+_+") (pintype "passive"))
      (node (ref "C36R") (pin "+") (pinfunction "+_+") (pintype "passive"))
      (node (ref "C37L") (pin "1") (pinfunction "1_1") (pintype "passive"))
      (node (ref "C37R") (pin "1") (pinfunction "1_1") (pintype "passive"))
      (node (ref "C38") (pin "2") (pinfunction "2_2") (pintype "passive"))
      (node (ref "C39") (pin "2") (pinfunction "2_2") (pintype "passive"))
      (node (ref "C4") (pin "2") (pinfunction "2_2") (pintype "passive"))
      (node (ref "C40") (pin "-") (pinfunction "-_-") (pintype "passive"))
      (node (ref "C41") (pin "1") (pinfunction "1_1") (pintype "passive"))
      (node (ref "C42L") (pin "-") (pinfunction "-_-") (pintype "passive"))
      (node (ref "C42R") (pin "-") (pinfunction "-_-") (pintype "passive"))
      (node (ref "C43L") (pin "2") (pinfunction "2_2") (pintype "passive"))
      (node (ref "C43R") (pin "2") (pinfunction "2_2") (pintype "passive"))
      (node (ref "C44L") (pin "2") (pinfunction "2_2") (pintype "passive"))
      (node (ref "C44R") (pin "2") (pinfunction "2_2") (pintype "passive"))
      (node (ref "C9") (pin "-") (pinfunction "-_-") (pintype "passive"))
      (node (ref "CI1L") (pin "2") (pinfunction "2_2") (pintype "passive"))
      (node (ref "CI1R") (pin "2") (pinfunction "2_2") (pintype "passive"))
      (node (ref "CI2L") (pin "1") (pinfunction "1_1") (pintype "passive"))
      (node (ref "CI2R") (pin "1") (pinfunction "1_1") (pintype "passive"))
      (node (ref "D10") (pin "A") (pinfunction "A_A") (pintype "passive"))
      (node (ref "D12") (pin "C") (pinfunction "C_C") (pintype "passive"))
      (node (ref "D2") (pin "A") (pinfunction "A_A") (pintype "passive"))
      (node (ref "D4") (pin "A") (pinfunction "A_A") (pintype "passive"))
      (node (ref "IC102") (pin "2") (pinfunction "C_2") (pintype "passive"))
      (node (ref "IC103") (pin "1") (pinfunction "A_1") (pintype "passive"))
      (node (ref "IC108") (pin "4") (pinfunction "EMIT_4") (pintype "passive"))
      (node (ref "IC109") (pin "4") (pinfunction "EMIT_4") (pintype "passive"))
      (node (ref "IC110") (pin "4") (pinfunction "EMIT_4") (pintype "passive"))
      (node (ref "IC111") (pin "4") (pinfunction "EMIT_4") (pintype "passive"))
      (node (ref "IC112") (pin "4") (pinfunction "EMIT_4") (pintype "passive"))
      (node (ref "IC2") (pin "2") (pinfunction "OUT_2") (pintype "passive"))
      (node (ref "IC3") (pin "2") (pinfunction "GND_2") (pintype "passive"))
      (node (ref "IC4L") (pin "11") (pinfunction "DGND_11") (pintype "bidirectional"))
      (node (ref "IC4L") (pin "16") (pinfunction "AGND_16") (pintype "bidirectional"))
      (node (ref "IC4R") (pin "11") (pinfunction "DGND_11") (pintype "bidirectional"))
      (node (ref "IC4R") (pin "16") (pinfunction "AGND_16") (pintype "bidirectional"))
      (node (ref "IC5L") (pin "3") (pinfunction "+IN_3") (pintype "input"))
      (node (ref "IC5R") (pin "3") (pinfunction "+IN_3") (pintype "input"))
      (node (ref "IC6L") (pin "3") (pinfunction "+IN_3") (pintype "input"))
      (node (ref "IC6R") (pin "3") (pinfunction "+IN_3") (pintype "input"))
      (node (ref "IC7") (pin "THERMAL") (pinfunction "THERMAL_THERMAL") (pintype "bidirectional"))
      (node (ref "J4") (pin "1") (pinfunction "1_1") (pintype "passive"))
      (node (ref "J6") (pin "G") (pinfunction "G_G") (pintype "bidirectional"))
      (node (ref "R15L") (pin "1") (pinfunction "1_1") (pintype "passive"))
      (node (ref "R15R") (pin "1") (pinfunction "1_1") (pintype "passive"))
      (node (ref "R3") (pin "E") (pinfunction "E_E") (pintype "passive"))
      (node (ref "R3") (pin "S") (pinfunction "S_S") (pintype "passive"))
      (node (ref "R4") (pin "2") (pinfunction "2_2") (pintype "passive"))
      (node (ref "R9L") (pin "2") (pinfunction "2_2") (pintype "passive"))
      (node (ref "R9R") (pin "2") (pinfunction "2_2") (pintype "passive"))
      (node (ref "REL102") (pin "S1") (pinfunction "S_S1") (pintype "passive"))
      (node (ref "REL102") (pin "S2") (pinfunction "S_S2") (pintype "passive"))
      (node (ref "T1") (pin "S") (pinfunction "S_S") (pintype "passive"))
      (node (ref "TP_GNDA") (pin "P$1") (pinfunction "P$1_P$1") (pintype "bidirectional"))
    )
    (net (code "31") (name "Net-(C1-Pad2)") (class "Default")
      (node (ref "C1") (pin "2") (pinfunction "2_2") (pintype "passive"))
      (node (ref "C2") (pin "1") (pinfunction "1_1") (pintype "passive"))
      (node (ref "D1") (pin "A") (pinfunction "A_A") (pintype "passive"))
      (node (ref "D2") (pin "C") (pinfunction "C_C") (pintype "passive"))
      (node (ref "J1") (pin "2") (pinfunction "2_2") (pintype "passive"))
    )
    (net (code "32") (name "Net-(C5-Pad2)") (class "Default")
      (node (ref "C5") (pin "2") (pinfunction "2_2") (pintype "passive"))
      (node (ref "C6") (pin "1") (pinfunction "1_1") (pintype "passive"))
      (node (ref "D6") (pin "A") (pinfunction "A_A") (pintype "passive"))
      (node (ref "D7") (pin "C") (pinfunction "C_C") (pintype "passive"))
      (node (ref "J2") (pin "1") (pinfunction "1_1") (pintype "passive"))
    )
    (net (code "33") (name "Net-(C45L-Pad2)") (class "Default")
      (node (ref "C45L") (pin "2") (pinfunction "2_2") (pintype "passive"))
      (node (ref "J5L") (pin "1") (pinfunction "1_1") (pintype "passive"))
    )
    (net (code "34") (name "Net-(C45R-Pad2)") (class "Default")
      (node (ref "C45R") (pin "2") (pinfunction "2_2") (pintype "passive"))
      (node (ref "J5R") (pin "1") (pinfunction "1_1") (pintype "passive"))
    )
    (net (code "35") (name "Net-(C46L-Pad1)") (class "Default")
      (node (ref "C46L") (pin "1") (pinfunction "1_1") (pintype "passive"))
      (node (ref "J5L") (pin "2") (pinfunction "2_2") (pintype "passive"))
    )
    (net (code "36") (name "Net-(C46R-Pad1)") (class "Default")
      (node (ref "C46R") (pin "1") (pinfunction "1_1") (pintype "passive"))
      (node (ref "J5R") (pin "2") (pinfunction "2_2") (pintype "passive"))
    )
    (net (code "37") (name "Net-(C109-Pad+)") (class "Default")
      (node (ref "C109") (pin "+") (pinfunction "+_+") (pintype "passive"))
      (node (ref "IC105") (pin "V+") (pinfunction "V+_V+") (pintype "bidirectional"))
      (node (ref "R112") (pin "1") (pinfunction "1_1") (pintype "passive"))
    )
    (net (code "38") (name "Net-(D101-PadA)") (class "Default")
      (node (ref "D101") (pin "A") (pinfunction "A_A") (pintype "passive"))
      (node (ref "R104") (pin "1") (pinfunction "1_1") (pintype "passive"))
    )
    (net (code "39") (name "Net-(D102-PadA)") (class "Default")
      (node (ref "D102") (pin "A") (pinfunction "A_A") (pintype "passive"))
      (node (ref "R105") (pin "1") (pinfunction "1_1") (pintype "passive"))
    )
    (net (code "40") (name "Net-(D103-PadA)") (class "Default")
      (node (ref "D103") (pin "A") (pinfunction "A_A") (pintype "passive"))
      (node (ref "R106") (pin "1") (pinfunction "1_1") (pintype "passive"))
    )
    (net (code "41") (name "Net-(F1-Pad2)") (class "Default")
      (node (ref "F1") (pin "2") (pinfunction "2_2") (pintype "bidirectional"))
      (node (ref "J1") (pin "1") (pinfunction "1_1") (pintype "passive"))
    )
    (net (code "42") (name "Net-(F2-Pad2)") (class "Default")
      (node (ref "F2") (pin "2") (pinfunction "2_2") (pintype "bidirectional"))
      (node (ref "J2") (pin "2") (pinfunction "2_2") (pintype "passive"))
    )
    (net (code "43") (name "Net-(F101-Pad1)") (class "Default")
      (node (ref "F101") (pin "1") (pinfunction "1_1") (pintype "bidirectional"))
      (node (ref "J101") (pin "2") (pinfunction "2_2") (pintype "passive"))
    )
    (net (code "44") (name "Net-(F101-Pad2)") (class "Default")
      (node (ref "F101") (pin "2") (pinfunction "2_2") (pintype "bidirectional"))
      (node (ref "M101") (pin "AC@1") (pinfunction "~_AC@1") (pintype "passive"))
    )
    (net (code "45") (name "Net-(IC1-ADJ)") (class "Default")
      (node (ref "C13") (pin "+") (pinfunction "+_+") (pintype "passive"))
      (node (ref "C14") (pin "+") (pinfunction "+_+") (pintype "passive"))
      (node (ref "C28") (pin "1") (pinfunction "1_1") (pintype "passive"))
      (node (ref "D11") (pin "A") (pinfunction "A_A") (pintype "passive"))
      (node (ref "IC1") (pin "1") (pinfunction "ADJ_1") (pintype "input"))
      (node (ref "R1") (pin "1") (pinfunction "1_1") (pintype "passive"))
      (node (ref "R2") (pin "1") (pinfunction "1_1") (pintype "passive"))
    )
    (net (code "46") (name "Net-(IC1-IN)") (class "Default")
      (node (ref "C1") (pin "1") (pinfunction "1_1") (pintype "passive"))
      (node (ref "C10") (pin "2") (pinfunction "2_2") (pintype "passive"))
      (node (ref "C3") (pin "1") (pinfunction "1_1") (pintype "passive"))
      (node (ref "C9") (pin "+") (pinfunction "+_+") (pintype "passive"))
      (node (ref "D1") (pin "C") (pinfunction "C_C") (pintype "passive"))
      (node (ref "D3") (pin "C") (pinfunction "C_C") (pintype "passive"))
      (node (ref "D5") (pin "C") (pinfunction "C_C") (pintype "passive"))
      (node (ref "IC1") (pin "3") (pinfunction "IN_3") (pintype "input"))
    )
    (net (code "47") (name "Net-(IC1-OUT)") (class "Default")
      (node (ref "C17") (pin "1") (pinfunction "1_1") (pintype "passive"))
      (node (ref "C18") (pin "+") (pinfunction "+_+") (pintype "passive"))
      (node (ref "C21") (pin "1") (pinfunction "1_1") (pintype "passive"))
      (node (ref "C22L") (pin "+") (pinfunction "+_+") (pintype "passive"))
      (node (ref "C22R") (pin "+") (pinfunction "+_+") (pintype "passive"))
      (node (ref "C23L") (pin "1") (pinfunction "1_1") (pintype "passive"))
      (node (ref "C23R") (pin "1") (pinfunction "1_1") (pintype "passive"))
      (node (ref "C26L") (pin "+") (pinfunction "+_+") (pintype "passive"))
      (node (ref "C26R") (pin "+") (pinfunction "+_+") (pintype "passive"))
      (node (ref "C27L") (pin "1") (pinfunction "1_1") (pintype "passive"))
      (node (ref "C27R") (pin "1") (pinfunction "1_1") (pintype "passive"))
      (node (ref "C30L") (pin "+") (pinfunction "+_+") (pintype "passive"))
      (node (ref "C30R") (pin "+") (pinfunction "+_+") (pintype "passive"))
      (node (ref "C31L") (pin "+") (pinfunction "+_+") (pintype "passive"))
      (node (ref "C31R") (pin "+") (pinfunction "+_+") (pintype "passive"))
      (node (ref "C32L") (pin "+") (pinfunction "+_+") (pintype "passive"))
      (node (ref "C32R") (pin "+") (pinfunction "+_+") (pintype "passive"))
      (node (ref "C33L") (pin "1") (pinfunction "1_1") (pintype "passive"))
      (node (ref "C33R") (pin "1") (pinfunction "1_1") (pintype "passive"))
      (node (ref "C38") (pin "1") (pinfunction "1_1") (pintype "passive"))
      (node (ref "CI1L") (pin "1") (pinfunction "1_1") (pintype "passive"))
      (node (ref "CI1R") (pin "1") (pinfunction "1_1") (pintype "passive"))
      (node (ref "D11") (pin "C") (pinfunction "C_C") (pintype "passive"))
      (node (ref "D5") (pin "A") (pinfunction "A_A") (pintype "passive"))
      (node (ref "IC1") (pin "2") (pinfunction "OUT_2") (pintype "passive"))
      (node (ref "IC3") (pin "1") (pinfunction "IN_1") (pintype "input"))
      (node (ref "IC5L") (pin "7") (pinfunction "V+_7") (pintype "power_in"))
      (node (ref "IC5R") (pin "7") (pinfunction "V+_7") (pintype "power_in"))
      (node (ref "IC6L") (pin "7") (pinfunction "V+_7") (pintype "power_in"))
      (node (ref "IC6R") (pin "7") (pinfunction "V+_7") (pintype "power_in"))
      (node (ref "IC7") (pin "18") (pinfunction "V+_18") (pintype "power_in"))
      (node (ref "IC7") (pin "3") (pinfunction "V+_3") (pintype "power_in"))
      (node (ref "R1") (pin "2") (pinfunction "2_2") (pintype "passive"))
      (node (ref "R7") (pin "2") (pinfunction "2_2") (pintype "passive"))
      (node (ref "TP_+12V") (pin "P$1") (pinfunction "P$1_P$1") (pintype "bidirectional"))
    )
    (net (code "48") (name "Net-(IC2-ADJ)") (class "Default")
      (node (ref "C15") (pin "+") (pinfunction "+_+") (pintype "passive"))
      (node (ref "C16") (pin "+") (pinfunction "+_+") (pintype "passive"))
      (node (ref "C29") (pin "1") (pinfunction "1_1") (pintype "passive"))
      (node (ref "D12") (pin "A") (pinfunction "A_A") (pintype "passive"))
      (node (ref "IC2") (pin "1") (pinfunction "ADJ_1") (pintype "input"))
      (node (ref "R4") (pin "1") (pinfunction "1_1") (pintype "passive"))
      (node (ref "R5") (pin "1") (pinfunction "1_1") (pintype "passive"))
    )
    (net (code "49") (name "Net-(IC2-IN)") (class "Default")
      (node (ref "C11") (pin "+") (pinfunction "+_+") (pintype "passive"))
      (node (ref "C12") (pin "2") (pinfunction "2_2") (pintype "passive"))
      (node (ref "C5") (pin "1") (pinfunction "1_1") (pintype "passive"))
      (node (ref "C7") (pin "1") (pinfunction "1_1") (pintype "passive"))
      (node (ref "D10") (pin "C") (pinfunction "C_C") (pintype "passive"))
      (node (ref "D6") (pin "C") (pinfunction "C_C") (pintype "passive"))
      (node (ref "D8") (pin "C") (pinfunction "C_C") (pintype "passive"))
      (node (ref "IC2") (pin "3") (pinfunction "IN_3") (pintype "input"))
    )
    (net (code "50") (name "Net-(IC4L-LFO)") (class "Default")
      (node (ref "IC4L") (pin "3") (pinfunction "LFO_3") (pintype "bidirectional"))
      (node (ref "IC5L") (pin "6") (pinfunction "OUT_6") (pintype "output"))
      (node (ref "R12L") (pin "1") (pinfunction "1_1") (pintype "passive"))
    )
    (net (code "51") (name "Net-(IC4L-LGND)") (class "Default")
      (node (ref "IC4L") (pin "12") (pinfunction "RGND_12") (pintype "bidirectional"))
      (node (ref "IC4L") (pin "5") (pinfunction "LGND_5") (pintype "bidirectional"))
      (node (ref "J5L") (pin "3") (pinfunction "3_3") (pintype "passive"))
      (node (ref "R9L") (pin "1") (pinfunction "1_1") (pintype "passive"))
    )
    (net (code "52") (name "Net-(IC4L-LIN)") (class "Default")
      (node (ref "C45L") (pin "1") (pinfunction "1_1") (pintype "passive"))
      (node (ref "IC4L") (pin "4") (pinfunction "LIN_4") (pintype "bidirectional"))
    )
    (net (code "53") (name "Net-(IC4L-LMO)") (class "Default")
      (node (ref "IC4L") (pin "2") (pinfunction "LMO_2") (pintype "bidirectional"))
      (node (ref "IC5L") (pin "2") (pinfunction "-IN_2") (pintype "input"))
    )
    (net (code "54") (name "Net-(IC4L-RFO)") (class "Default")
      (node (ref "IC4L") (pin "14") (pinfunction "RFO_14") (pintype "bidirectional"))
      (node (ref "IC6L") (pin "6") (pinfunction "OUT_6") (pintype "output"))
      (node (ref "R13L") (pin "1") (pinfunction "1_1") (pintype "passive"))
    )
    (net (code "55") (name "Net-(IC4L-RIN)") (class "Default")
      (node (ref "C46L") (pin "2") (pinfunction "2_2") (pintype "passive"))
      (node (ref "IC4L") (pin "13") (pinfunction "RIN_13") (pintype "bidirectional"))
    )
    (net (code "56") (name "Net-(IC4L-RMO)") (class "Default")
      (node (ref "IC4L") (pin "15") (pinfunction "RMO_15") (pintype "bidirectional"))
      (node (ref "IC6L") (pin "2") (pinfunction "-IN_2") (pintype "input"))
    )
    (net (code "57") (name "Net-(IC4R-LFO)") (class "Default")
      (node (ref "IC4R") (pin "3") (pinfunction "LFO_3") (pintype "bidirectional"))
      (node (ref "IC5R") (pin "6") (pinfunction "OUT_6") (pintype "output"))
      (node (ref "R12R") (pin "1") (pinfunction "1_1") (pintype "passive"))
    )
    (net (code "58") (name "Net-(IC4R-LGND)") (class "Default")
      (node (ref "IC4R") (pin "12") (pinfunction "RGND_12") (pintype "bidirectional"))
      (node (ref "IC4R") (pin "5") (pinfunction "LGND_5") (pintype "bidirectional"))
      (node (ref "J5R") (pin "3") (pinfunction "3_3") (pintype "passive"))
      (node (ref "R9R") (pin "1") (pinfunction "1_1") (pintype "passive"))
    )
    (net (code "59") (name "Net-(IC4R-LIN)") (class "Default")
      (node (ref "C45R") (pin "1") (pinfunction "1_1") (pintype "passive"))
      (node (ref "IC4R") (pin "4") (pinfunction "LIN_4") (pintype "bidirectional"))
    )
    (net (code "60") (name "Net-(IC4R-LMO)") (class "Default")
      (node (ref "IC4R") (pin "2") (pinfunction "LMO_2") (pintype "bidirectional"))
      (node (ref "IC5R") (pin "2") (pinfunction "-IN_2") (pintype "input"))
    )
    (net (code "61") (name "Net-(IC4R-RFO)") (class "Default")
      (node (ref "IC4R") (pin "14") (pinfunction "RFO_14") (pintype "bidirectional"))
      (node (ref "IC6R") (pin "6") (pinfunction "OUT_6") (pintype "output"))
      (node (ref "R13R") (pin "1") (pinfunction "1_1") (pintype "passive"))
    )
    (net (code "62") (name "Net-(IC4R-RIN)") (class "Default")
      (node (ref "C46R") (pin "2") (pinfunction "2_2") (pintype "passive"))
      (node (ref "IC4R") (pin "13") (pinfunction "RIN_13") (pintype "bidirectional"))
    )
    (net (code "63") (name "Net-(IC4R-RMO)") (class "Default")
      (node (ref "IC4R") (pin "15") (pinfunction "RMO_15") (pintype "bidirectional"))
      (node (ref "IC6R") (pin "2") (pinfunction "-IN_2") (pintype "input"))
    )
    (net (code "64") (name "Net-(IC5LB-V-)") (class "Default")
      (node (ref "C11") (pin "-") (pinfunction "-_-") (pintype "passive"))
      (node (ref "C12") (pin "1") (pinfunction "1_1") (pintype "passive"))
      (node (ref "C15") (pin "-") (pinfunction "-_-") (pintype "passive"))
      (node (ref "C16") (pin "-") (pinfunction "-_-") (pintype "passive"))
      (node (ref "C19") (pin "2") (pinfunction "2_2") (pintype "passive"))
      (node (ref "C20") (pin "-") (pinfunction "-_-") (pintype "passive"))
      (node (ref "C21") (pin "2") (pinfunction "2_2") (pintype "passive"))
      (node (ref "C24L") (pin "-") (pinfunction "-_-") (pintype "passive"))
      (node (ref "C24R") (pin "-") (pinfunction "-_-") (pintype "passive"))
      (node (ref "C25L") (pin "2") (pinfunction "2_2") (pintype "passive"))
      (node (ref "C25R") (pin "2") (pinfunction "2_2") (pintype "passive"))
      (node (ref "C28L") (pin "-") (pinfunction "-_-") (pintype "passive"))
      (node (ref "C28R") (pin "-") (pinfunction "-_-") (pintype "passive"))
      (node (ref "C29") (pin "2") (pinfunction "2_2") (pintype "passive"))
      (node (ref "C29L") (pin "2") (pinfunction "2_2") (pintype "passive"))
      (node (ref "C29R") (pin "2") (pinfunction "2_2") (pintype "passive"))
      (node (ref "C34L") (pin "-") (pinfunction "-_-") (pintype "passive"))
      (node (ref "C34R") (pin "-") (pinfunction "-_-") (pintype "passive"))
      (node (ref "C35L") (pin "-") (pinfunction "-_-") (pintype "passive"))
      (node (ref "C35R") (pin "-") (pinfunction "-_-") (pintype "passive"))
      (node (ref "C36L") (pin "-") (pinfunction "-_-") (pintype "passive"))
      (node (ref "C36R") (pin "-") (pinfunction "-_-") (pintype "passive"))
      (node (ref "C37L") (pin "2") (pinfunction "2_2") (pintype "passive"))
      (node (ref "C37R") (pin "2") (pinfunction "2_2") (pintype "passive"))
      (node (ref "C6") (pin "2") (pinfunction "2_2") (pintype "passive"))
      (node (ref "C8") (pin "2") (pinfunction "2_2") (pintype "passive"))
      (node (ref "CI2L") (pin "2") (pinfunction "2_2") (pintype "passive"))
      (node (ref "CI2R") (pin "2") (pinfunction "2_2") (pintype "passive"))
      (node (ref "D7") (pin "A") (pinfunction "A_A") (pintype "passive"))
      (node (ref "D9") (pin "A") (pinfunction "A_A") (pintype "passive"))
      (node (ref "IC5L") (pin "4") (pinfunction "V-_4") (pintype "power_in"))
      (node (ref "IC5R") (pin "4") (pinfunction "V-_4") (pintype "power_in"))
      (node (ref "IC6L") (pin "4") (pinfunction "V-_4") (pintype "power_in"))
      (node (ref "IC6R") (pin "4") (pinfunction "V-_4") (pintype "power_in"))
      (node (ref "IC7") (pin "1") (pinfunction "V-_1") (pintype "power_in"))
      (node (ref "IC7") (pin "20") (pinfunction "V-_20") (pintype "power_in"))
      (node (ref "R6") (pin "E") (pinfunction "E_E") (pintype "passive"))
      (node (ref "R6") (pin "S") (pinfunction "S_S") (pintype "passive"))
      (node (ref "R8") (pin "2") (pinfunction "2_2") (pintype "passive"))
      (node (ref "TP_-12V") (pin "P$1") (pinfunction "P$1_P$1") (pintype "bidirectional"))
    )
    (net (code "65") (name "Net-(IC7A-IN+)") (class "Default")
      (node (ref "IC7") (pin "4") (pinfunction "IN+_4") (pintype "input"))
      (node (ref "R13L") (pin "2") (pinfunction "2_2") (pintype "passive"))
      (node (ref "R15L") (pin "2") (pinfunction "2_2") (pintype "passive"))
    )
    (net (code "66") (name "Net-(IC7A-IN-)") (class "Default")
      (node (ref "IC7") (pin "5") (pinfunction "IN-_5") (pintype "input"))
      (node (ref "R12L") (pin "2") (pinfunction "2_2") (pintype "passive"))
      (node (ref "R14L") (pin "1") (pinfunction "1_1") (pintype "passive"))
    )
    (net (code "67") (name "Net-(IC7A-OUT)") (class "Default")
      (node (ref "IC7") (pin "2") (pinfunction "OUT_2") (pintype "output"))
      (node (ref "R14L") (pin "2") (pinfunction "2_2") (pintype "passive"))
      (node (ref "R16L") (pin "2") (pinfunction "2_2") (pintype "passive"))
    )
    (net (code "68") (name "Net-(IC7C-IN+)") (class "Default")
      (node (ref "IC7") (pin "17") (pinfunction "IN+_17") (pintype "input"))
      (node (ref "R13R") (pin "2") (pinfunction "2_2") (pintype "passive"))
      (node (ref "R15R") (pin "2") (pinfunction "2_2") (pintype "passive"))
    )
    (net (code "69") (name "Net-(IC7C-IN-)") (class "Default")
      (node (ref "IC7") (pin "16") (pinfunction "IN-_16") (pintype "input"))
      (node (ref "R12R") (pin "2") (pinfunction "2_2") (pintype "passive"))
      (node (ref "R14R") (pin "1") (pinfunction "1_1") (pintype "passive"))
    )
    (net (code "70") (name "Net-(IC7C-OUT)") (class "Default")
      (node (ref "IC7") (pin "19") (pinfunction "OUT_19") (pintype "output"))
      (node (ref "R14R") (pin "2") (pinfunction "2_2") (pintype "passive"))
      (node (ref "R16R") (pin "2") (pinfunction "2_2") (pintype "passive"))
    )
    (net (code "71") (name "Net-(IC101-IN)") (class "Default")
      (node (ref "C101") (pin "+") (pinfunction "+_+") (pintype "passive"))
      (node (ref "C102") (pin "1") (pinfunction "1_1") (pintype "passive"))
      (node (ref "IC101") (pin "1") (pinfunction "IN_1") (pintype "input"))
      (node (ref "M101") (pin "+") (pinfunction "+_+") (pintype "passive"))
    )
    (net (code "72") (name "Net-(IC102-A)") (class "Default")
      (node (ref "IC102") (pin "1") (pinfunction "A_1") (pintype "passive"))
      (node (ref "R7") (pin "1") (pinfunction "1_1") (pintype "passive"))
    )
    (net (code "73") (name "Net-(IC102-COL)") (class "Default")
      (node (ref "IC102") (pin "5") (pinfunction "COL_5") (pintype "passive"))
      (node (ref "R101") (pin "2") (pinfunction "2_2") (pintype "passive"))
    )
    (net (code "74") (name "Net-(IC103-C)") (class "Default")
      (node (ref "IC103") (pin "2") (pinfunction "C_2") (pintype "passive"))
      (node (ref "R8") (pin "1") (pinfunction "1_1") (pintype "passive"))
    )
    (net (code "75") (name "Net-(IC103-COL)") (class "Default")
      (node (ref "IC103") (pin "5") (pinfunction "COL_5") (pintype "passive"))
      (node (ref "R102") (pin "2") (pinfunction "2_2") (pintype "passive"))
    )
    (net (code "76") (name "Net-(IC106-AREF)") (class "Default")
      (node (ref "C106") (pin "1") (pinfunction "1_1") (pintype "passive"))
      (node (ref "IC106") (pin "21") (pinfunction "AREF_21") (pintype "passive"))
    )
    (net (code "77") (name "Net-(IC106-AVCC)") (class "Default")
      (node (ref "IC106") (pin "20") (pinfunction "AVCC_20") (pintype "power_in"))
      (node (ref "R120") (pin "1") (pinfunction "1_1") (pintype "passive"))
    )
    (net (code "78") (name "Net-(IC106-PB6)") (class "Default")
      (node (ref "C107") (pin "1") (pinfunction "1_1") (pintype "passive"))
      (node (ref "IC106") (pin "9") (pinfunction "PB6_9") (pintype "bidirectional"))
      (node (ref "X101") (pin "1") (pinfunction "1_1") (pintype "passive"))
    )
    (net (code "79") (name "Net-(IC106-PB7)") (class "Default")
      (node (ref "C108") (pin "1") (pinfunction "1_1") (pintype "passive"))
      (node (ref "IC106") (pin "10") (pinfunction "PB7_10") (pintype "bidirectional"))
      (node (ref "X101") (pin "2") (pinfunction "2_2") (pintype "passive"))
    )
    (net (code "80") (name "Net-(IC107-A)") (class "Default")
      (node (ref "IC107") (pin "1") (pinfunction "A_1") (pintype "passive"))
      (node (ref "R18") (pin "2") (pinfunction "2_2") (pintype "passive"))
    )
    (net (code "81") (name "Net-(IC107-C)") (class "Default")
      (node (ref "IC107") (pin "2") (pinfunction "C_2") (pintype "passive"))
      (node (ref "T1") (pin "D") (pinfunction "D_D") (pintype "passive"))
    )
    (net (code "82") (name "Net-(IC108-A)") (class "Default")
      (node (ref "IC108") (pin "1") (pinfunction "A_1") (pintype "passive"))
      (node (ref "R115") (pin "1") (pinfunction "1_1") (pintype "passive"))
    )
    (net (code "83") (name "Net-(IC109-A)") (class "Default")
      (node (ref "IC109") (pin "1") (pinfunction "A_1") (pintype "passive"))
      (node (ref "R116") (pin "1") (pinfunction "1_1") (pintype "passive"))
    )
    (net (code "84") (name "Net-(IC110-A)") (class "Default")
      (node (ref "IC110") (pin "1") (pinfunction "A_1") (pintype "passive"))
      (node (ref "R117") (pin "1") (pinfunction "1_1") (pintype "passive"))
    )
    (net (code "85") (name "Net-(IC111-A)") (class "Default")
      (node (ref "IC111") (pin "1") (pinfunction "A_1") (pintype "passive"))
      (node (ref "R118") (pin "1") (pinfunction "1_1") (pintype "passive"))
    )
    (net (code "86") (name "Net-(IC112-A)") (class "Default")
      (node (ref "IC112") (pin "1") (pinfunction "A_1") (pintype "passive"))
      (node (ref "R119") (pin "1") (pinfunction "1_1") (pintype "passive"))
    )
    (net (code "87") (name "Net-(IC113-A)") (class "Default")
      (node (ref "IC113") (pin "1") (pinfunction "A_1") (pintype "passive"))
      (node (ref "R24") (pin "2") (pinfunction "2_2") (pintype "passive"))
    )
    (net (code "88") (name "Net-(J101-Pad1)") (class "Default")
      (node (ref "J101") (pin "1") (pinfunction "1_1") (pintype "passive"))
      (node (ref "M101") (pin "AC@2") (pinfunction "~_AC@2") (pintype "passive"))
    )
    (net (code "89") (name "Net-(J103-RXD)") (class "Default")
      (node (ref "J103") (pin "6") (pinfunction "RXD_6") (pintype "bidirectional"))
      (node (ref "J106") (pin "2") (pinfunction "2_2") (pintype "passive"))
      (node (ref "R108") (pin "2") (pinfunction "2_2") (pintype "passive"))
    )
    (net (code "90") (name "Net-(J103-TXD)") (class "Default")
      (node (ref "J103") (pin "4") (pinfunction "TXD_4") (pintype "bidirectional"))
      (node (ref "J106") (pin "3") (pinfunction "3_3") (pintype "passive"))
      (node (ref "R107") (pin "2") (pinfunction "2_2") (pintype "passive"))
    )
    (net (code "91") (name "Net-(R2-Pad2)") (class "Default")
      (node (ref "R2") (pin "2") (pinfunction "2_2") (pintype "passive"))
      (node (ref "R3") (pin "A") (pinfunction "A_A") (pintype "passive"))
    )
    (net (code "92") (name "Net-(R5-Pad2)") (class "Default")
      (node (ref "R5") (pin "2") (pinfunction "2_2") (pintype "passive"))
      (node (ref "R6") (pin "A") (pinfunction "A_A") (pintype "passive"))
    )
    (net (code "93") (name "Net-(R17-Pad2)") (class "Default")
      (node (ref "R17") (pin "2") (pinfunction "2_2") (pintype "passive"))
      (node (ref "T1") (pin "G") (pinfunction "G_G") (pintype "passive"))
    )
    (net (code "94") (name "Net-(R109-Pad2)") (class "Default")
      (node (ref "R109") (pin "2") (pinfunction "2_2") (pintype "passive"))
      (node (ref "T2") (pin "G") (pinfunction "G_G") (pintype "passive"))
    )
    (net (code "95") (name "Net-(R110-Pad2)") (class "Default")
      (node (ref "R110") (pin "2") (pinfunction "2_2") (pintype "passive"))
      (node (ref "T3") (pin "G") (pinfunction "G_G") (pintype "passive"))
    )
    (net (code "96") (name "Net-(REL101A-2)") (class "Default")
      (node (ref "D104") (pin "A") (pinfunction "A_A") (pintype "passive"))
      (node (ref "REL101") (pin "10") (pinfunction "2_10") (pintype "passive"))
      (node (ref "T2") (pin "D") (pinfunction "D_D") (pintype "passive"))
    )
    (net (code "97") (name "Net-(REL101B-P)") (class "Default")
      (node (ref "F2") (pin "1") (pinfunction "1_1") (pintype "bidirectional"))
      (node (ref "REL101") (pin "P1") (pinfunction "P_P1") (pintype "passive"))
    )
    (net (code "98") (name "Net-(REL101B-S)") (class "Default")
      (node (ref "C7") (pin "2") (pinfunction "2_2") (pintype "passive"))
      (node (ref "C8") (pin "1") (pinfunction "1_1") (pintype "passive"))
      (node (ref "D8") (pin "A") (pinfunction "A_A") (pintype "passive"))
      (node (ref "D9") (pin "C") (pinfunction "C_C") (pintype "passive"))
      (node (ref "REL101") (pin "S1") (pinfunction "S_S1") (pintype "passive"))
    )
    (net (code "99") (name "Net-(REL101C-P)") (class "Default")
      (node (ref "F1") (pin "1") (pinfunction "1_1") (pintype "bidirectional"))
      (node (ref "REL101") (pin "P2") (pinfunction "P_P2") (pintype "passive"))
    )
    (net (code "100") (name "Net-(REL101C-S)") (class "Default")
      (node (ref "C3") (pin "2") (pinfunction "2_2") (pintype "passive"))
      (node (ref "C4") (pin "1") (pinfunction "1_1") (pintype "passive"))
      (node (ref "D3") (pin "A") (pinfunction "A_A") (pintype "passive"))
      (node (ref "D4") (pin "C") (pinfunction "C_C") (pintype "passive"))
      (node (ref "REL101") (pin "S2") (pinfunction "S_S2") (pintype "passive"))
    )
    (net (code "101") (name "Net-(REL102A-2)") (class "Default")
      (node (ref "D105") (pin "A") (pinfunction "A_A") (pintype "passive"))
      (node (ref "REL102") (pin "10") (pinfunction "2_10") (pintype "passive"))
      (node (ref "T3") (pin "D") (pinfunction "D_D") (pintype "passive"))
    )
    (net (code "102") (name "Net-(REL102B-O)") (class "Default")
      (node (ref "R16R") (pin "1") (pinfunction "1_1") (pintype "passive"))
      (node (ref "REL102") (pin "O1") (pinfunction "O_O1") (pintype "passive"))
    )
    (net (code "103") (name "Net-(REL102B-P)") (class "Default")
      (node (ref "J6") (pin "R") (pinfunction "R_R") (pintype "bidirectional"))
      (node (ref "REL102") (pin "P1") (pinfunction "P_P1") (pintype "passive"))
    )
    (net (code "104") (name "Net-(REL102C-O)") (class "Default")
      (node (ref "R16L") (pin "1") (pinfunction "1_1") (pintype "passive"))
      (node (ref "REL102") (pin "O2") (pinfunction "O_O2") (pintype "passive"))
    )
    (net (code "105") (name "Net-(REL102C-P)") (class "Default")
      (node (ref "J6") (pin "L") (pinfunction "L_L") (pintype "bidirectional"))
      (node (ref "REL102") (pin "P2") (pinfunction "P_P2") (pintype "passive"))
    )
    (net (code "106") (name "VCC") (class "Default")
      (node (ref "C103") (pin "1") (pinfunction "1_1") (pintype "passive"))
      (node (ref "C104") (pin "+") (pinfunction "+_+") (pintype "passive"))
      (node (ref "C105") (pin "1") (pinfunction "1_1") (pintype "passive"))
      (node (ref "D104") (pin "C") (pinfunction "C_C") (pintype "passive"))
      (node (ref "D105") (pin "C") (pinfunction "C_C") (pintype "passive"))
      (node (ref "IC101") (pin "3") (pinfunction "OUT_3") (pintype "passive"))
      (node (ref "IC106") (pin "7") (pinfunction "VCC_7") (pintype "power_in"))
      (node (ref "J103") (pin "2") (pinfunction "VCC_2") (pintype "power_in"))
      (node (ref "J105") (pin "8") (pinfunction "8_8") (pintype "passive"))
      (node (ref "R103") (pin "1") (pinfunction "1_1") (pintype "passive"))
      (node (ref "R104") (pin "2") (pinfunction "2_2") (pintype "passive"))
      (node (ref "R105") (pin "2") (pinfunction "2_2") (pintype "passive"))
      (node (ref "R106") (pin "2") (pinfunction "2_2") (pintype "passive"))
      (node (ref "R112") (pin "2") (pinfunction "2_2") (pintype "passive"))
      (node (ref "R113") (pin "1") (pinfunction "1_1") (pintype "passive"))
      (node (ref "R115") (pin "2") (pinfunction "2_2") (pintype "passive"))
      (node (ref "R116") (pin "2") (pinfunction "2_2") (pintype "passive"))
      (node (ref "R117") (pin "2") (pinfunction "2_2") (pintype "passive"))
      (node (ref "R118") (pin "2") (pinfunction "2_2") (pintype "passive"))
      (node (ref "R119") (pin "2") (pinfunction "2_2") (pintype "passive"))
      (node (ref "R120") (pin "2") (pinfunction "2_2") (pintype "passive"))
      (node (ref "REL101") (pin "1") (pinfunction "1_1") (pintype "passive"))
      (node (ref "REL102") (pin "1") (pinfunction "1_1") (pintype "passive"))
    )
    (net (code "107") (name "unconnected-(IC5LA-O1-Pad1)") (class "Default")
      (node (ref "IC5L") (pin "1") (pinfunction "O1_1") (pintype "bidirectional"))
    )
    (net (code "108") (name "unconnected-(IC5LA-O8-Pad8)") (class "Default")
      (node (ref "IC5L") (pin "8") (pinfunction "O8_8") (pintype "bidirectional"))
    )
    (net (code "109") (name "unconnected-(IC5RA-O1-Pad1)") (class "Default")
      (node (ref "IC5R") (pin "1") (pinfunction "O1_1") (pintype "bidirectional"))
    )
    (net (code "110") (name "unconnected-(IC5RA-O8-Pad8)") (class "Default")
      (node (ref "IC5R") (pin "8") (pinfunction "O8_8") (pintype "bidirectional"))
    )
    (net (code "111") (name "unconnected-(IC6LA-O1-Pad1)") (class "Default")
      (node (ref "IC6L") (pin "1") (pinfunction "O1_1") (pintype "bidirectional"))
    )
    (net (code "112") (name "unconnected-(IC6LA-O8-Pad8)") (class "Default")
      (node (ref "IC6L") (pin "8") (pinfunction "O8_8") (pintype "bidirectional"))
    )
    (net (code "113") (name "unconnected-(IC6RA-O1-Pad1)") (class "Default")
      (node (ref "IC6R") (pin "1") (pinfunction "O1_1") (pintype "bidirectional"))
    )
    (net (code "114") (name "unconnected-(IC6RA-O8-Pad8)") (class "Default")
      (node (ref "IC6R") (pin "8") (pinfunction "O8_8") (pintype "bidirectional"))
    )
    (net (code "115") (name "unconnected-(J6-PadLOFF)") (class "Default")
      (node (ref "J6") (pin "LOFF") (pinfunction "LOFF_LOFF") (pintype "bidirectional"))
    )
    (net (code "116") (name "unconnected-(J6-PadROFF)") (class "Default")
      (node (ref "J6") (pin "ROFF") (pinfunction "ROFF_ROFF") (pintype "bidirectional"))
    )
    (net (code "117") (name "unconnected-(REL101B-O-PadO1)") (class "Default")
      (node (ref "REL101") (pin "O1") (pinfunction "O_O1") (pintype "passive"))
    )
    (net (code "118") (name "unconnected-(REL101C-O-PadO2)") (class "Default")
      (node (ref "REL101") (pin "O2") (pinfunction "O_O2") (pintype "passive"))
    )
  )
)
